# MCU.net
KiCad netlist of a schematic drawn in Altium Designer
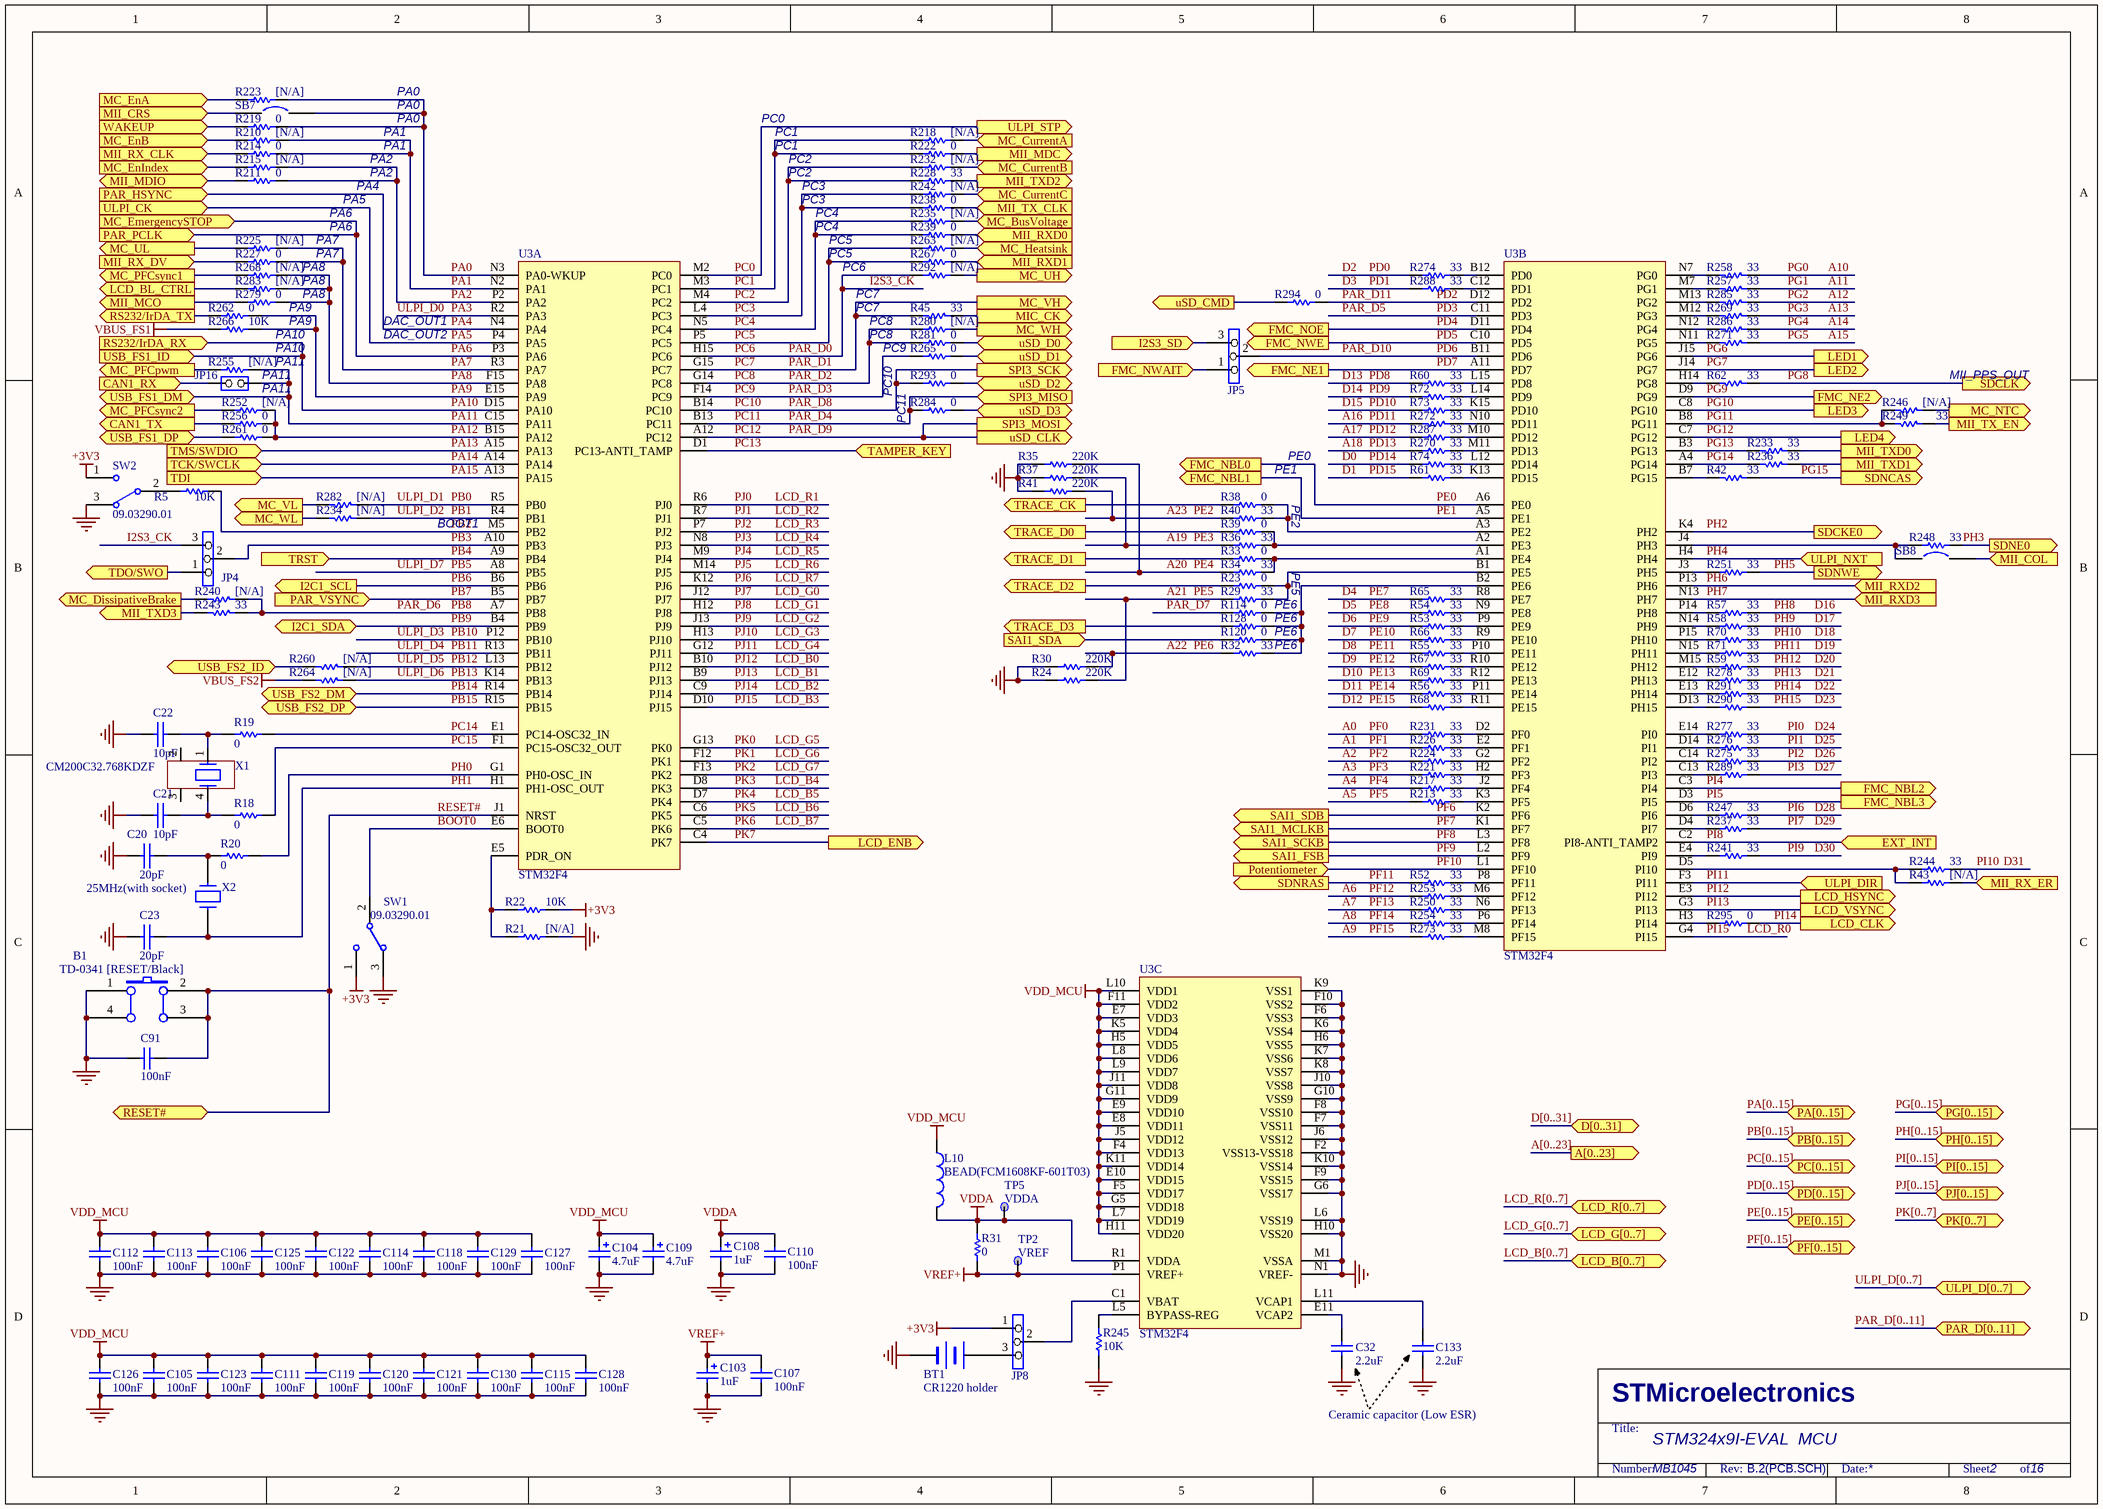
[diagram p0: MCU.SchDoc]

(export (version "E")
  (design (tool "Eeschema 10.0.6"))
  (components
    (comp (ref "B1")
      (value "TD-0341 [RESET/Black]")
      (footprint "PB10")
      (description "SE PUSHBUTTON")
      (libsource (lib "Documents") (part "SW PUSHBUTTON"))
    )
    (comp (ref "BT1")
      (value "CR1220 holder")
      (footprint "BAT_2SM_CR1220")
      (description "Battery")
      (libsource (lib "*") (part "BATTERY"))
    )
    (comp (ref "C20")
      (value "20pF")
      (footprint "0603C")
      (description "Capacitor")
      (libsource (lib "*") (part "CAP"))
    )
    (comp (ref "C21")
      (value "10pF")
      (footprint "0603C")
      (description "Capacitor")
      (libsource (lib "") (part "CAP_1"))
    )
    (comp (ref "C22")
      (value "10pF")
      (footprint "0603C")
      (description "Capacitor")
      (libsource (lib "") (part "CAP_1"))
    )
    (comp (ref "C23")
      (value "20pF")
      (footprint "0603C")
      (description "Capacitor")
      (libsource (lib "*") (part "CAP"))
    )
    (comp (ref "C32")
      (value "2.2uF")
      (footprint "1206C")
      (description "Capacitor")
      (fields (field (name "PUBLISHER") "Altium Limited"))
      (libsource (lib "Miscellaneous Devices") (part "Cap"))
    )
    (comp (ref "C91")
      (value "100nF")
      (footprint "0603C")
      (description "Capacitor")
      (fields (field (name "PUBLISHER") "Altium Limited"))
      (libsource (lib "Miscellaneous Devices") (part "CAP"))
    )
    (comp (ref "C103")
      (value "1uF")
      (footprint "TAN-A")
      (description "Polarized Capacitor (Radial)")
      (fields (field (name "PUBLISHER") "Altium Limited"))
      (libsource (lib "Miscellaneous Devices") (part "Cap Pol1"))
    )
    (comp (ref "C104")
      (value "4.7uF")
      (footprint "TAN-A")
      (description "Polarized Capacitor (Radial)")
      (fields (field (name "PUBLISHER") "Altium Limited"))
      (libsource (lib "Miscellaneous Devices") (part "Cap Pol1"))
    )
    (comp (ref "C105")
      (value "100nF")
      (footprint "0402C")
      (description "Capacitor")
      (fields (field (name "PUBLISHER") "Altium Limited"))
      (libsource (lib "Miscellaneous Devices") (part "CAP"))
    )
    (comp (ref "C106")
      (value "100nF")
      (footprint "0402C")
      (description "Capacitor")
      (fields (field (name "PUBLISHER") "Altium Limited"))
      (libsource (lib "Miscellaneous Devices") (part "CAP"))
    )
    (comp (ref "C107")
      (value "100nF")
      (footprint "0402C")
      (description "Capacitor")
      (fields (field (name "PUBLISHER") "Altium Limited"))
      (libsource (lib "Miscellaneous Devices") (part "Cap"))
    )
    (comp (ref "C108")
      (value "1uF")
      (footprint "TAN-A")
      (description "Polarized Capacitor (Radial)")
      (fields (field (name "PUBLISHER") "Altium Limited"))
      (libsource (lib "Miscellaneous Devices") (part "Cap Pol1"))
    )
    (comp (ref "C109")
      (value "4.7uF")
      (footprint "TAN-A")
      (description "Polarized Capacitor (Radial)")
      (fields (field (name "PUBLISHER") "Altium Limited"))
      (libsource (lib "Miscellaneous Devices") (part "Cap Pol1"))
    )
    (comp (ref "C110")
      (value "100nF")
      (footprint "0402C")
      (description "Capacitor")
      (fields (field (name "PUBLISHER") "Altium Limited"))
      (libsource (lib "Miscellaneous Devices") (part "Cap"))
    )
    (comp (ref "C111")
      (value "100nF")
      (footprint "0402C")
      (description "Capacitor")
      (fields (field (name "PUBLISHER") "Altium Limited"))
      (libsource (lib "Miscellaneous Devices") (part "CAP"))
    )
    (comp (ref "C112")
      (value "100nF")
      (footprint "0402C")
      (description "Capacitor")
      (fields (field (name "PUBLISHER") "Altium Limited"))
      (libsource (lib "Miscellaneous Devices") (part "CAP"))
    )
    (comp (ref "C113")
      (value "100nF")
      (footprint "0402C")
      (description "Capacitor")
      (fields (field (name "PUBLISHER") "Altium Limited"))
      (libsource (lib "Miscellaneous Devices") (part "CAP"))
    )
    (comp (ref "C114")
      (value "100nF")
      (footprint "0402C")
      (description "Capacitor")
      (fields (field (name "PUBLISHER") "Altium Limited"))
      (libsource (lib "Miscellaneous Devices") (part "CAP"))
    )
    (comp (ref "C115")
      (value "100nF")
      (footprint "0402C")
      (description "Capacitor")
      (fields (field (name "PUBLISHER") "Altium Limited"))
      (libsource (lib "Miscellaneous Devices") (part "CAP"))
    )
    (comp (ref "C118")
      (value "100nF")
      (footprint "0402C")
      (description "Capacitor")
      (fields (field (name "PUBLISHER") "Altium Limited"))
      (libsource (lib "Miscellaneous Devices") (part "CAP"))
    )
    (comp (ref "C119")
      (value "100nF")
      (footprint "0402C")
      (description "Capacitor")
      (fields (field (name "PUBLISHER") "Altium Limited"))
      (libsource (lib "Miscellaneous Devices") (part "CAP"))
    )
    (comp (ref "C120")
      (value "100nF")
      (footprint "0402C")
      (description "Capacitor")
      (fields (field (name "PUBLISHER") "Altium Limited"))
      (libsource (lib "Miscellaneous Devices") (part "CAP"))
    )
    (comp (ref "C121")
      (value "100nF")
      (footprint "0402C")
      (description "Capacitor")
      (fields (field (name "PUBLISHER") "Altium Limited"))
      (libsource (lib "Miscellaneous Devices") (part "CAP"))
    )
    (comp (ref "C122")
      (value "100nF")
      (footprint "0402C")
      (description "Capacitor")
      (fields (field (name "PUBLISHER") "Altium Limited"))
      (libsource (lib "Miscellaneous Devices") (part "CAP"))
    )
    (comp (ref "C123")
      (value "100nF")
      (footprint "0402C")
      (description "Capacitor")
      (fields (field (name "PUBLISHER") "Altium Limited"))
      (libsource (lib "Miscellaneous Devices") (part "CAP"))
    )
    (comp (ref "C125")
      (value "100nF")
      (footprint "0402C")
      (description "Capacitor")
      (fields (field (name "PUBLISHER") "Altium Limited"))
      (libsource (lib "Miscellaneous Devices") (part "CAP"))
    )
    (comp (ref "C126")
      (value "100nF")
      (footprint "0402C")
      (description "Capacitor")
      (fields (field (name "PUBLISHER") "Altium Limited"))
      (libsource (lib "Miscellaneous Devices") (part "CAP"))
    )
    (comp (ref "C127")
      (value "100nF")
      (footprint "0402C")
      (description "Capacitor")
      (fields (field (name "PUBLISHER") "Altium Limited"))
      (libsource (lib "Miscellaneous Devices") (part "CAP"))
    )
    (comp (ref "C128")
      (value "100nF")
      (footprint "0402C")
      (description "Capacitor")
      (fields (field (name "PUBLISHER") "Altium Limited"))
      (libsource (lib "Miscellaneous Devices") (part "CAP"))
    )
    (comp (ref "C129")
      (value "100nF")
      (footprint "0402C")
      (description "Capacitor")
      (fields (field (name "PUBLISHER") "Altium Limited"))
      (libsource (lib "Miscellaneous Devices") (part "CAP"))
    )
    (comp (ref "C130")
      (value "100nF")
      (footprint "0402C")
      (description "Capacitor")
      (fields (field (name "PUBLISHER") "Altium Limited"))
      (libsource (lib "Miscellaneous Devices") (part "CAP"))
    )
    (comp (ref "C133")
      (value "2.2uF")
      (footprint "1206C")
      (description "Capacitor")
      (fields (field (name "PUBLISHER") "Altium Limited"))
      (libsource (lib "Miscellaneous Devices") (part "Cap"))
    )
    (comp (ref "JP4") (value "~") (footprint "SIP3") (libsource (lib "") (part "Jumper3_1")))
    (comp (ref "JP5") (value "~") (footprint "SIP3") (libsource (lib "") (part "Jumper3_1")))
    (comp (ref "JP8") (value "~") (footprint "SIP3") (libsource (lib "STR910_SCHLIB") (part "Jumper3")))
    (comp (ref "JP16") (value "~") (footprint "SIP2") (libsource (lib "*") (part "JP2")))
    (comp (ref "L10")
      (value "BEAD(FCM1608KF-601T03)")
      (footprint "0603L")
      (description "Inductor")
      (fields (field (name "PUBLISHER") "Altium Limited"))
      (libsource (lib "Miscellaneous Devices") (part "Inductor"))
    )
    (comp (ref "R5")
      (value "10K")
      (footprint "0603R")
      (description "Resistor")
      (fields (field (name "PUBLISHER") "Altium Limited"))
      (libsource (lib "Miscellaneous Devices") (part "Res1"))
    )
    (comp (ref "R18")
      (value "0")
      (footprint "0603R")
      (description "Resistor")
      (fields (field (name "PUBLISHER") "Altium Limited"))
      (libsource (lib "") (part "Res1_1"))
    )
    (comp (ref "R19")
      (value "0")
      (footprint "0603R")
      (description "Resistor")
      (fields (field (name "PUBLISHER") "Altium Limited"))
      (libsource (lib "") (part "Res1_1"))
    )
    (comp (ref "R20")
      (value "0")
      (footprint "0603R")
      (description "Resistor")
      (fields (field (name "PUBLISHER") "Altium Limited"))
      (libsource (lib "Miscellaneous Devices") (part "Res1"))
    )
    (comp (ref "R21")
      (value "[N/A]")
      (footprint "0603R")
      (description "Resistor")
      (fields (field (name "PUBLISHER") "Altium Limited"))
      (libsource (lib "Miscellaneous Devices") (part "Res1"))
    )
    (comp (ref "R22")
      (value "10K")
      (footprint "0603R")
      (description "Resistor")
      (fields (field (name "PUBLISHER") "Altium Limited"))
      (libsource (lib "Miscellaneous Devices") (part "Res1"))
    )
    (comp (ref "R23")
      (value "0")
      (footprint "0603R")
      (description "Resistor")
      (fields (field (name "PUBLISHER") "Altium Limited"))
      (libsource (lib "Miscellaneous Devices") (part "Res1"))
    )
    (comp (ref "R24")
      (value "220K")
      (footprint "0603R")
      (description "Resistor")
      (fields (field (name "PUBLISHER") "Altium Limited"))
      (libsource (lib "Miscellaneous Devices") (part "res1"))
    )
    (comp (ref "R29")
      (value "33")
      (footprint "0402R")
      (description "Resistor")
      (fields (field (name "PUBLISHER") "Altium Limited"))
      (libsource (lib "Miscellaneous Devices") (part "Res1"))
    )
    (comp (ref "R30")
      (value "220K")
      (footprint "0603R")
      (description "Resistor")
      (fields (field (name "PUBLISHER") "Altium Limited"))
      (libsource (lib "Miscellaneous Devices") (part "res1"))
    )
    (comp (ref "R31")
      (value "0")
      (footprint "0603R")
      (description "Resistor")
      (fields (field (name "PUBLISHER") "Altium Limited"))
      (libsource (lib "Miscellaneous Devices") (part "Res1"))
    )
    (comp (ref "R32")
      (value "33")
      (footprint "0402R")
      (description "Resistor")
      (fields (field (name "PUBLISHER") "Altium Limited"))
      (libsource (lib "Miscellaneous Devices") (part "Res1"))
    )
    (comp (ref "R33")
      (value "0")
      (footprint "0603R")
      (description "Resistor")
      (fields (field (name "PUBLISHER") "Altium Limited"))
      (libsource (lib "Miscellaneous Devices") (part "Res1"))
    )
    (comp (ref "R34")
      (value "33")
      (footprint "0402R")
      (description "Resistor")
      (fields (field (name "PUBLISHER") "Altium Limited"))
      (libsource (lib "Miscellaneous Devices") (part "Res1"))
    )
    (comp (ref "R35")
      (value "220K")
      (footprint "0603R")
      (description "Resistor")
      (fields (field (name "PUBLISHER") "Altium Limited"))
      (libsource (lib "Miscellaneous Devices") (part "res1"))
    )
    (comp (ref "R36")
      (value "33")
      (footprint "0402R")
      (description "Resistor")
      (fields (field (name "PUBLISHER") "Altium Limited"))
      (libsource (lib "Miscellaneous Devices") (part "Res1"))
    )
    (comp (ref "R37")
      (value "220K")
      (footprint "0603R")
      (description "Resistor")
      (fields (field (name "PUBLISHER") "Altium Limited"))
      (libsource (lib "Miscellaneous Devices") (part "res1"))
    )
    (comp (ref "R38")
      (value "0")
      (footprint "0603R")
      (description "Resistor")
      (fields (field (name "PUBLISHER") "Altium Limited"))
      (libsource (lib "Miscellaneous Devices") (part "Res1"))
    )
    (comp (ref "R39")
      (value "0")
      (footprint "0603R")
      (description "Resistor")
      (fields (field (name "PUBLISHER") "Altium Limited"))
      (libsource (lib "Miscellaneous Devices") (part "Res1"))
    )
    (comp (ref "R40")
      (value "33")
      (footprint "0402R")
      (description "Resistor")
      (fields (field (name "PUBLISHER") "Altium Limited"))
      (libsource (lib "Miscellaneous Devices") (part "Res1"))
    )
    (comp (ref "R41")
      (value "220K")
      (footprint "0603R")
      (description "Resistor")
      (fields (field (name "PUBLISHER") "Altium Limited"))
      (libsource (lib "Miscellaneous Devices") (part "res1"))
    )
    (comp (ref "R42")
      (value "33")
      (footprint "0402R")
      (description "Resistor")
      (fields (field (name "PUBLISHER") "Altium Limited"))
      (libsource (lib "Miscellaneous Devices") (part "Res1"))
    )
    (comp (ref "R43")
      (value "[N/A]")
      (footprint "0603R")
      (description "Resistor")
      (fields (field (name "PUBLISHER") "Altium Limited"))
      (libsource (lib "Miscellaneous Devices") (part "Res1"))
    )
    (comp (ref "R45")
      (value "33")
      (footprint "0603R")
      (description "Resistor")
      (fields (field (name "PUBLISHER") "Altium Limited"))
      (libsource (lib "Miscellaneous Devices") (part "Res1"))
    )
    (comp (ref "R52")
      (value "33")
      (footprint "0402R")
      (description "Resistor")
      (fields (field (name "PUBLISHER") "Altium Limited"))
      (libsource (lib "Miscellaneous Devices") (part "Res1"))
    )
    (comp (ref "R53")
      (value "33")
      (footprint "0402R")
      (description "Resistor")
      (fields (field (name "PUBLISHER") "Altium Limited"))
      (libsource (lib "Miscellaneous Devices") (part "Res1"))
    )
    (comp (ref "R54")
      (value "33")
      (footprint "0402R")
      (description "Resistor")
      (fields (field (name "PUBLISHER") "Altium Limited"))
      (libsource (lib "Miscellaneous Devices") (part "Res1"))
    )
    (comp (ref "R55")
      (value "33")
      (footprint "0402R")
      (description "Resistor")
      (fields (field (name "PUBLISHER") "Altium Limited"))
      (libsource (lib "Miscellaneous Devices") (part "Res1"))
    )
    (comp (ref "R56")
      (value "33")
      (footprint "0402R")
      (description "Resistor")
      (fields (field (name "PUBLISHER") "Altium Limited"))
      (libsource (lib "Miscellaneous Devices") (part "Res1"))
    )
    (comp (ref "R57")
      (value "33")
      (footprint "0402R")
      (description "Resistor")
      (fields (field (name "PUBLISHER") "Altium Limited"))
      (libsource (lib "Miscellaneous Devices") (part "Res1"))
    )
    (comp (ref "R58")
      (value "33")
      (footprint "0402R")
      (description "Resistor")
      (fields (field (name "PUBLISHER") "Altium Limited"))
      (libsource (lib "Miscellaneous Devices") (part "Res1"))
    )
    (comp (ref "R59")
      (value "33")
      (footprint "0402R")
      (description "Resistor")
      (fields (field (name "PUBLISHER") "Altium Limited"))
      (libsource (lib "Miscellaneous Devices") (part "Res1"))
    )
    (comp (ref "R60")
      (value "33")
      (footprint "0402R")
      (description "Resistor")
      (fields (field (name "PUBLISHER") "Altium Limited"))
      (libsource (lib "Miscellaneous Devices") (part "Res1"))
    )
    (comp (ref "R61")
      (value "33")
      (footprint "0402R")
      (description "Resistor")
      (fields (field (name "PUBLISHER") "Altium Limited"))
      (libsource (lib "Miscellaneous Devices") (part "Res1"))
    )
    (comp (ref "R62")
      (value "33")
      (footprint "0402R")
      (description "Resistor")
      (fields (field (name "PUBLISHER") "Altium Limited"))
      (libsource (lib "Miscellaneous Devices") (part "Res1"))
    )
    (comp (ref "R65")
      (value "33")
      (footprint "0402R")
      (description "Resistor")
      (fields (field (name "PUBLISHER") "Altium Limited"))
      (libsource (lib "Miscellaneous Devices") (part "Res1"))
    )
    (comp (ref "R66")
      (value "33")
      (footprint "0402R")
      (description "Resistor")
      (fields (field (name "PUBLISHER") "Altium Limited"))
      (libsource (lib "Miscellaneous Devices") (part "Res1"))
    )
    (comp (ref "R67")
      (value "33")
      (footprint "0402R")
      (description "Resistor")
      (fields (field (name "PUBLISHER") "Altium Limited"))
      (libsource (lib "Miscellaneous Devices") (part "Res1"))
    )
    (comp (ref "R68")
      (value "33")
      (footprint "0402R")
      (description "Resistor")
      (fields (field (name "PUBLISHER") "Altium Limited"))
      (libsource (lib "Miscellaneous Devices") (part "Res1"))
    )
    (comp (ref "R69")
      (value "33")
      (footprint "0402R")
      (description "Resistor")
      (fields (field (name "PUBLISHER") "Altium Limited"))
      (libsource (lib "Miscellaneous Devices") (part "Res1"))
    )
    (comp (ref "R70")
      (value "33")
      (footprint "0402R")
      (description "Resistor")
      (fields (field (name "PUBLISHER") "Altium Limited"))
      (libsource (lib "Miscellaneous Devices") (part "Res1"))
    )
    (comp (ref "R71")
      (value "33")
      (footprint "0402R")
      (description "Resistor")
      (fields (field (name "PUBLISHER") "Altium Limited"))
      (libsource (lib "Miscellaneous Devices") (part "Res1"))
    )
    (comp (ref "R72")
      (value "33")
      (footprint "0402R")
      (description "Resistor")
      (fields (field (name "PUBLISHER") "Altium Limited"))
      (libsource (lib "Miscellaneous Devices") (part "Res1"))
    )
    (comp (ref "R73")
      (value "33")
      (footprint "0402R")
      (description "Resistor")
      (fields (field (name "PUBLISHER") "Altium Limited"))
      (libsource (lib "Miscellaneous Devices") (part "Res1"))
    )
    (comp (ref "R74")
      (value "33")
      (footprint "0402R")
      (description "Resistor")
      (fields (field (name "PUBLISHER") "Altium Limited"))
      (libsource (lib "Miscellaneous Devices") (part "Res1"))
    )
    (comp (ref "R114")
      (value "0")
      (footprint "0603R")
      (description "Resistor")
      (fields (field (name "PUBLISHER") "Altium Limited"))
      (libsource (lib "Miscellaneous Devices") (part "Res1"))
    )
    (comp (ref "R120")
      (value "0")
      (footprint "0603R")
      (description "Resistor")
      (fields (field (name "PUBLISHER") "Altium Limited"))
      (libsource (lib "Miscellaneous Devices") (part "Res1"))
    )
    (comp (ref "R128")
      (value "0")
      (footprint "0603R")
      (description "Resistor")
      (fields (field (name "PUBLISHER") "Altium Limited"))
      (libsource (lib "Miscellaneous Devices") (part "Res1"))
    )
    (comp (ref "R210")
      (value "[N/A]")
      (footprint "0603R")
      (description "Resistor")
      (fields (field (name "PUBLISHER") "Altium Limited"))
      (libsource (lib "Miscellaneous Devices") (part "Res1"))
    )
    (comp (ref "R211")
      (value "0")
      (footprint "0603R")
      (description "Resistor")
      (fields (field (name "PUBLISHER") "Altium Limited"))
      (libsource (lib "Miscellaneous Devices") (part "Res1"))
    )
    (comp (ref "R213")
      (value "33")
      (footprint "0402R")
      (description "Resistor")
      (fields (field (name "PUBLISHER") "Altium Limited"))
      (libsource (lib "Miscellaneous Devices") (part "Res1"))
    )
    (comp (ref "R214")
      (value "0")
      (footprint "0603R")
      (description "Resistor")
      (fields (field (name "PUBLISHER") "Altium Limited"))
      (libsource (lib "Miscellaneous Devices") (part "Res1"))
    )
    (comp (ref "R215")
      (value "[N/A]")
      (footprint "0603R")
      (description "Resistor")
      (fields (field (name "PUBLISHER") "Altium Limited"))
      (libsource (lib "Miscellaneous Devices") (part "Res1"))
    )
    (comp (ref "R217")
      (value "33")
      (footprint "0402R")
      (description "Resistor")
      (fields (field (name "PUBLISHER") "Altium Limited"))
      (libsource (lib "Miscellaneous Devices") (part "Res1"))
    )
    (comp (ref "R218")
      (value "[N/A]")
      (footprint "0603R")
      (description "Resistor")
      (fields (field (name "PUBLISHER") "Altium Limited"))
      (libsource (lib "Miscellaneous Devices") (part "Res1"))
    )
    (comp (ref "R219")
      (value "0")
      (footprint "0603R")
      (description "Resistor")
      (fields (field (name "PUBLISHER") "Altium Limited"))
      (libsource (lib "Miscellaneous Devices") (part "Res1"))
    )
    (comp (ref "R221")
      (value "33")
      (footprint "0402R")
      (description "Resistor")
      (fields (field (name "PUBLISHER") "Altium Limited"))
      (libsource (lib "Miscellaneous Devices") (part "Res1"))
    )
    (comp (ref "R222")
      (value "0")
      (footprint "0603R")
      (description "Resistor")
      (fields (field (name "PUBLISHER") "Altium Limited"))
      (libsource (lib "Miscellaneous Devices") (part "Res1"))
    )
    (comp (ref "R223")
      (value "[N/A]")
      (footprint "0603R")
      (description "Resistor")
      (fields (field (name "PUBLISHER") "Altium Limited"))
      (libsource (lib "Miscellaneous Devices") (part "Res1"))
    )
    (comp (ref "R224")
      (value "33")
      (footprint "0402R")
      (description "Resistor")
      (fields (field (name "PUBLISHER") "Altium Limited"))
      (libsource (lib "Miscellaneous Devices") (part "Res1"))
    )
    (comp (ref "R225")
      (value "[N/A]")
      (footprint "0603R")
      (description "Resistor")
      (fields (field (name "PUBLISHER") "Altium Limited"))
      (libsource (lib "Miscellaneous Devices") (part "Res1"))
    )
    (comp (ref "R226")
      (value "33")
      (footprint "0402R")
      (description "Resistor")
      (fields (field (name "PUBLISHER") "Altium Limited"))
      (libsource (lib "Miscellaneous Devices") (part "Res1"))
    )
    (comp (ref "R227")
      (value "0")
      (footprint "0603R")
      (description "Resistor")
      (fields (field (name "PUBLISHER") "Altium Limited"))
      (libsource (lib "Miscellaneous Devices") (part "Res1"))
    )
    (comp (ref "R228")
      (value "33")
      (footprint "0603R")
      (description "Resistor")
      (fields (field (name "PUBLISHER") "Altium Limited"))
      (libsource (lib "Miscellaneous Devices") (part "Res1"))
    )
    (comp (ref "R231")
      (value "33")
      (footprint "0402R")
      (description "Resistor")
      (fields (field (name "PUBLISHER") "Altium Limited"))
      (libsource (lib "Miscellaneous Devices") (part "Res1"))
    )
    (comp (ref "R232")
      (value "[N/A]")
      (footprint "0603R")
      (description "Resistor")
      (fields (field (name "PUBLISHER") "Altium Limited"))
      (libsource (lib "Miscellaneous Devices") (part "Res1"))
    )
    (comp (ref "R233")
      (value "33")
      (footprint "0603R")
      (description "Resistor")
      (fields (field (name "PUBLISHER") "Altium Limited"))
      (libsource (lib "Miscellaneous Devices") (part "Res1"))
    )
    (comp (ref "R234")
      (value "[N/A]")
      (footprint "0603R")
      (description "Resistor")
      (fields (field (name "PUBLISHER") "Altium Limited"))
      (libsource (lib "Miscellaneous Devices") (part "Res1"))
    )
    (comp (ref "R235")
      (value "[N/A]")
      (footprint "0603R")
      (description "Resistor")
      (fields (field (name "PUBLISHER") "Altium Limited"))
      (libsource (lib "Miscellaneous Devices") (part "Res1"))
    )
    (comp (ref "R236")
      (value "33")
      (footprint "0603R")
      (description "Resistor")
      (fields (field (name "PUBLISHER") "Altium Limited"))
      (libsource (lib "Miscellaneous Devices") (part "Res1"))
    )
    (comp (ref "R237")
      (value "33")
      (footprint "0402R")
      (description "Resistor")
      (fields (field (name "PUBLISHER") "Altium Limited"))
      (libsource (lib "Miscellaneous Devices") (part "Res1"))
    )
    (comp (ref "R238")
      (value "0")
      (footprint "0603R")
      (description "Resistor")
      (fields (field (name "PUBLISHER") "Altium Limited"))
      (libsource (lib "Miscellaneous Devices") (part "Res1"))
    )
    (comp (ref "R239")
      (value "0")
      (footprint "0603R")
      (description "Resistor")
      (fields (field (name "PUBLISHER") "Altium Limited"))
      (libsource (lib "Miscellaneous Devices") (part "Res1"))
    )
    (comp (ref "R240")
      (value "[N/A]")
      (footprint "0603R")
      (description "Resistor")
      (fields (field (name "PUBLISHER") "Altium Limited"))
      (libsource (lib "Miscellaneous Devices") (part "Res1"))
    )
    (comp (ref "R241")
      (value "33")
      (footprint "0402R")
      (description "Resistor")
      (fields (field (name "PUBLISHER") "Altium Limited"))
      (libsource (lib "Miscellaneous Devices") (part "Res1"))
    )
    (comp (ref "R242")
      (value "[N/A]")
      (footprint "0603R")
      (description "Resistor")
      (fields (field (name "PUBLISHER") "Altium Limited"))
      (libsource (lib "Miscellaneous Devices") (part "Res1"))
    )
    (comp (ref "R243")
      (value "33")
      (footprint "0603R")
      (description "Resistor")
      (fields (field (name "PUBLISHER") "Altium Limited"))
      (libsource (lib "Miscellaneous Devices") (part "Res1"))
    )
    (comp (ref "R244")
      (value "33")
      (footprint "0402R")
      (description "Resistor")
      (fields (field (name "PUBLISHER") "Altium Limited"))
      (libsource (lib "Miscellaneous Devices") (part "Res1"))
    )
    (comp (ref "R245")
      (value "10K")
      (footprint "0603R")
      (description "Resistor")
      (fields (field (name "PUBLISHER") "Altium Limited"))
      (libsource (lib "Miscellaneous Devices") (part "Res1"))
    )
    (comp (ref "R246")
      (value "[N/A]")
      (footprint "0603R")
      (description "Resistor")
      (fields (field (name "PUBLISHER") "Altium Limited"))
      (libsource (lib "Miscellaneous Devices") (part "Res1"))
    )
    (comp (ref "R247")
      (value "33")
      (footprint "0402R")
      (description "Resistor")
      (fields (field (name "PUBLISHER") "Altium Limited"))
      (libsource (lib "Miscellaneous Devices") (part "Res1"))
    )
    (comp (ref "R248")
      (value "33")
      (footprint "0402R")
      (description "Resistor")
      (fields (field (name "PUBLISHER") "Altium Limited"))
      (libsource (lib "Miscellaneous Devices") (part "Res1"))
    )
    (comp (ref "R249")
      (value "33")
      (footprint "0603R")
      (description "Resistor")
      (fields (field (name "PUBLISHER") "Altium Limited"))
      (libsource (lib "Miscellaneous Devices") (part "Res1"))
    )
    (comp (ref "R250")
      (value "33")
      (footprint "0402R")
      (description "Resistor")
      (fields (field (name "PUBLISHER") "Altium Limited"))
      (libsource (lib "Miscellaneous Devices") (part "Res1"))
    )
    (comp (ref "R251")
      (value "33")
      (footprint "0402R")
      (description "Resistor")
      (fields (field (name "PUBLISHER") "Altium Limited"))
      (libsource (lib "Miscellaneous Devices") (part "Res1"))
    )
    (comp (ref "R252")
      (value "[N/A]")
      (footprint "0603R")
      (description "Resistor")
      (fields (field (name "PUBLISHER") "Altium Limited"))
      (libsource (lib "Miscellaneous Devices") (part "Res1"))
    )
    (comp (ref "R253")
      (value "33")
      (footprint "0402R")
      (description "Resistor")
      (fields (field (name "PUBLISHER") "Altium Limited"))
      (libsource (lib "Miscellaneous Devices") (part "Res1"))
    )
    (comp (ref "R254")
      (value "33")
      (footprint "0402R")
      (description "Resistor")
      (fields (field (name "PUBLISHER") "Altium Limited"))
      (libsource (lib "Miscellaneous Devices") (part "Res1"))
    )
    (comp (ref "R255")
      (value "[N/A]")
      (footprint "0603R")
      (description "Resistor")
      (fields (field (name "PUBLISHER") "Altium Limited"))
      (libsource (lib "Miscellaneous Devices") (part "Res1"))
    )
    (comp (ref "R256")
      (value "0")
      (footprint "0603R")
      (description "Resistor")
      (fields (field (name "PUBLISHER") "Altium Limited"))
      (libsource (lib "Miscellaneous Devices") (part "Res1"))
    )
    (comp (ref "R257")
      (value "33")
      (footprint "0402R")
      (description "Resistor")
      (fields (field (name "PUBLISHER") "Altium Limited"))
      (libsource (lib "Miscellaneous Devices") (part "Res1"))
    )
    (comp (ref "R258")
      (value "33")
      (footprint "0402R")
      (description "Resistor")
      (fields (field (name "PUBLISHER") "Altium Limited"))
      (libsource (lib "Miscellaneous Devices") (part "Res1"))
    )
    (comp (ref "R260")
      (value "[N/A]")
      (footprint "0603R")
      (description "Resistor")
      (fields (field (name "PUBLISHER") "Altium Limited"))
      (libsource (lib "Miscellaneous Devices") (part "Res1"))
    )
    (comp (ref "R261")
      (value "0")
      (footprint "0603R")
      (description "Resistor")
      (fields (field (name "PUBLISHER") "Altium Limited"))
      (libsource (lib "Miscellaneous Devices") (part "Res1"))
    )
    (comp (ref "R262")
      (value "0")
      (footprint "0603R")
      (description "Resistor")
      (fields (field (name "PUBLISHER") "Altium Limited"))
      (libsource (lib "Miscellaneous Devices") (part "Res1"))
    )
    (comp (ref "R263")
      (value "[N/A]")
      (footprint "0603R")
      (description "Resistor")
      (fields (field (name "PUBLISHER") "Altium Limited"))
      (libsource (lib "Miscellaneous Devices") (part "Res1"))
    )
    (comp (ref "R264")
      (value "[N/A]")
      (footprint "0603R")
      (description "Resistor")
      (fields (field (name "PUBLISHER") "Altium Limited"))
      (libsource (lib "Miscellaneous Devices") (part "Res1"))
    )
    (comp (ref "R265")
      (value "0")
      (footprint "0603R")
      (description "Resistor")
      (fields (field (name "PUBLISHER") "Altium Limited"))
      (libsource (lib "Miscellaneous Devices") (part "Res1"))
    )
    (comp (ref "R266")
      (value "10K")
      (footprint "0603R")
      (description "Resistor")
      (fields (field (name "PUBLISHER") "Altium Limited"))
      (libsource (lib "Miscellaneous Devices") (part "res1"))
    )
    (comp (ref "R267")
      (value "0")
      (footprint "0603R")
      (description "Resistor")
      (fields (field (name "PUBLISHER") "Altium Limited"))
      (libsource (lib "Miscellaneous Devices") (part "Res1"))
    )
    (comp (ref "R268")
      (value "[N/A]")
      (footprint "0603R")
      (description "Resistor")
      (fields (field (name "PUBLISHER") "Altium Limited"))
      (libsource (lib "Miscellaneous Devices") (part "Res1"))
    )
    (comp (ref "R269")
      (value "33")
      (footprint "0402R")
      (description "Resistor")
      (fields (field (name "PUBLISHER") "Altium Limited"))
      (libsource (lib "Miscellaneous Devices") (part "Res1"))
    )
    (comp (ref "R270")
      (value "33")
      (footprint "0402R")
      (description "Resistor")
      (fields (field (name "PUBLISHER") "Altium Limited"))
      (libsource (lib "Miscellaneous Devices") (part "Res1"))
    )
    (comp (ref "R271")
      (value "33")
      (footprint "0402R")
      (description "Resistor")
      (fields (field (name "PUBLISHER") "Altium Limited"))
      (libsource (lib "Miscellaneous Devices") (part "Res1"))
    )
    (comp (ref "R272")
      (value "33")
      (footprint "0402R")
      (description "Resistor")
      (fields (field (name "PUBLISHER") "Altium Limited"))
      (libsource (lib "Miscellaneous Devices") (part "Res1"))
    )
    (comp (ref "R273")
      (value "33")
      (footprint "0402R")
      (description "Resistor")
      (fields (field (name "PUBLISHER") "Altium Limited"))
      (libsource (lib "Miscellaneous Devices") (part "Res1"))
    )
    (comp (ref "R274")
      (value "33")
      (footprint "0402R")
      (description "Resistor")
      (fields (field (name "PUBLISHER") "Altium Limited"))
      (libsource (lib "Miscellaneous Devices") (part "Res1"))
    )
    (comp (ref "R275")
      (value "33")
      (footprint "0402R")
      (description "Resistor")
      (fields (field (name "PUBLISHER") "Altium Limited"))
      (libsource (lib "Miscellaneous Devices") (part "Res1"))
    )
    (comp (ref "R276")
      (value "33")
      (footprint "0402R")
      (description "Resistor")
      (fields (field (name "PUBLISHER") "Altium Limited"))
      (libsource (lib "Miscellaneous Devices") (part "Res1"))
    )
    (comp (ref "R277")
      (value "33")
      (footprint "0402R")
      (description "Resistor")
      (fields (field (name "PUBLISHER") "Altium Limited"))
      (libsource (lib "Miscellaneous Devices") (part "Res1"))
    )
    (comp (ref "R278")
      (value "33")
      (footprint "0402R")
      (description "Resistor")
      (fields (field (name "PUBLISHER") "Altium Limited"))
      (libsource (lib "Miscellaneous Devices") (part "Res1"))
    )
    (comp (ref "R279")
      (value "0")
      (footprint "0603R")
      (description "Resistor")
      (fields (field (name "PUBLISHER") "Altium Limited"))
      (libsource (lib "Miscellaneous Devices") (part "Res1"))
    )
    (comp (ref "R280")
      (value "[N/A]")
      (footprint "0603R")
      (description "Resistor")
      (fields (field (name "PUBLISHER") "Altium Limited"))
      (libsource (lib "Miscellaneous Devices") (part "Res1"))
    )
    (comp (ref "R281")
      (value "0")
      (footprint "0603R")
      (description "Resistor")
      (fields (field (name "PUBLISHER") "Altium Limited"))
      (libsource (lib "Miscellaneous Devices") (part "Res1"))
    )
    (comp (ref "R282")
      (value "[N/A]")
      (footprint "0603R")
      (description "Resistor")
      (fields (field (name "PUBLISHER") "Altium Limited"))
      (libsource (lib "Miscellaneous Devices") (part "Res1"))
    )
    (comp (ref "R283")
      (value "[N/A]")
      (footprint "0603R")
      (description "Resistor")
      (fields (field (name "PUBLISHER") "Altium Limited"))
      (libsource (lib "Miscellaneous Devices") (part "Res1"))
    )
    (comp (ref "R284")
      (value "0")
      (footprint "0603R")
      (description "Resistor")
      (fields (field (name "PUBLISHER") "Altium Limited"))
      (libsource (lib "Miscellaneous Devices") (part "Res1"))
    )
    (comp (ref "R285")
      (value "33")
      (footprint "0402R")
      (description "Resistor")
      (fields (field (name "PUBLISHER") "Altium Limited"))
      (libsource (lib "Miscellaneous Devices") (part "Res1"))
    )
    (comp (ref "R286")
      (value "33")
      (footprint "0402R")
      (description "Resistor")
      (fields (field (name "PUBLISHER") "Altium Limited"))
      (libsource (lib "Miscellaneous Devices") (part "Res1"))
    )
    (comp (ref "R287")
      (value "33")
      (footprint "0402R")
      (description "Resistor")
      (fields (field (name "PUBLISHER") "Altium Limited"))
      (libsource (lib "Miscellaneous Devices") (part "Res1"))
    )
    (comp (ref "R288")
      (value "33")
      (footprint "0402R")
      (description "Resistor")
      (fields (field (name "PUBLISHER") "Altium Limited"))
      (libsource (lib "Miscellaneous Devices") (part "Res1"))
    )
    (comp (ref "R289")
      (value "33")
      (footprint "0402R")
      (description "Resistor")
      (fields (field (name "PUBLISHER") "Altium Limited"))
      (libsource (lib "Miscellaneous Devices") (part "Res1"))
    )
    (comp (ref "R290")
      (value "33")
      (footprint "0402R")
      (description "Resistor")
      (fields (field (name "PUBLISHER") "Altium Limited"))
      (libsource (lib "Miscellaneous Devices") (part "Res1"))
    )
    (comp (ref "R291")
      (value "33")
      (footprint "0402R")
      (description "Resistor")
      (fields (field (name "PUBLISHER") "Altium Limited"))
      (libsource (lib "Miscellaneous Devices") (part "Res1"))
    )
    (comp (ref "R292")
      (value "[N/A]")
      (footprint "0603R")
      (description "Resistor")
      (fields (field (name "PUBLISHER") "Altium Limited"))
      (libsource (lib "Miscellaneous Devices") (part "Res1"))
    )
    (comp (ref "R293")
      (value "0")
      (footprint "0603R")
      (description "Resistor")
      (fields (field (name "PUBLISHER") "Altium Limited"))
      (libsource (lib "Miscellaneous Devices") (part "Res1"))
    )
    (comp (ref "R294")
      (value "0")
      (footprint "0603R")
      (description "Resistor")
      (fields (field (name "PUBLISHER") "Altium Limited"))
      (libsource (lib "Miscellaneous Devices") (part "Res1"))
    )
    (comp (ref "R295")
      (value "0")
      (footprint "0603R")
      (description "Resistor")
      (fields (field (name "PUBLISHER") "Altium Limited"))
      (libsource (lib "Miscellaneous Devices") (part "Res1"))
    )
    (comp (ref "SB7")
      (value "~")
      (footprint "JP2_SMD")
      (description "Circuit Breaker")
      (fields (field (name "PUBLISHER") "Altium Limited"))
      (libsource (lib "Miscellaneous Devices") (part "Circuit Breaker"))
    )
    (comp (ref "SB8")
      (value "~")
      (footprint "JP2_SMD")
      (description "Circuit Breaker")
      (fields (field (name "PUBLISHER") "Altium Limited"))
      (libsource (lib "Miscellaneous Devices") (part "Circuit Breaker"))
    )
    (comp (ref "SW1")
      (value "09.03290.01")
      (footprint "SW1_3TH_2R54_10X2R5")
      (description "SPDT Subminiature Toggle Switch, Right Angle Mounting, Vertical Actuation")
      (fields (field (name "PUBLISHER") "Altium Limited"))
      (libsource (lib "mb1045") (part "SW-SPDT"))
    )
    (comp (ref "SW2")
      (value "09.03290.01")
      (footprint "SW1_3TH_2R54_10X2R5")
      (description "SPDT Subminiature Toggle Switch, Right Angle Mounting, Vertical Actuation")
      (fields (field (name "PUBLISHER") "Altium Limited"))
      (libsource (lib "mb1045") (part "SW-SPDT"))
    )
    (comp (ref "TP2") (value "VREF") (footprint "TP") (libsource (lib "*") (part "TP")))
    (comp (ref "TP5") (value "VDDA") (footprint "TP") (libsource (lib "*") (part "TP")))
    (comp (ref "U3")
      (value "STM32F4")
      (footprint "BGA216_0R8_13X13_SKT")
      (libsource (lib "mb1045") (part "Big_Manta_TFBGA216"))
    )
    (comp (ref "X1")
      (value "CM200C32.768KDZF")
      (footprint "XTAL_4SM_8X3R8")
      (libsource (lib "*") (part "MC306"))
    )
    (comp (ref "X2")
      (value "25MHz(with socket)")
      (footprint "XTAL_socket")
      (description "Crystal")
      (libsource (lib "*") (part "CRYSTAL"))
    )
  )
  (nets
    (net (code "1") (name "+3V3") (class "Default")
      (node (ref "JP8") (pin "1") (pintype "passive"))
      (node (ref "R22") (pin "2") (pinfunction "2_2") (pintype "passive"))
      (node (ref "SW1") (pin "1") (pintype "passive"))
      (node (ref "SW2") (pin "1") (pintype "passive"))
    )
    (net (code "3") (name "/BOOT0") (class "Default")
      (node (ref "SW1") (pin "2") (pintype "passive"))
      (node (ref "U3") (pin "E6") (pinfunction "BOOT0_E6") (pintype "passive"))
    )
    (net (code "4") (name "/CAN1_RX") (class "Default")
      (node (ref "JP16") (pin "2") (pinfunction "NO_2") (pintype "passive"))
    )
    (net (code "5") (name "/CAN1_TX") (class "Default")
      (node (ref "R256") (pin "2") (pinfunction "2_2") (pintype "passive"))
    )
    (net (code "7") (name "/FMC_NWAIT") (class "Default") (node (ref "JP5") (pin "1") (pintype "passive")))
    (net (code "8") (name "/I2S3_SD") (class "Default") (node (ref "JP5") (pin "3") (pintype "passive")))
    (net (code "9") (name "/LCD_BL_CTRL") (class "Default")
      (node (ref "R283") (pin "2") (pinfunction "2_2") (pintype "passive"))
    )
    (net (code "13") (name "/MC_BusVoltage") (class "Default")
      (node (ref "R235") (pin "1") (pinfunction "1_1") (pintype "passive"))
    )
    (net (code "14") (name "/MC_CurrentA") (class "Default")
      (node (ref "R218") (pin "1") (pinfunction "1_1") (pintype "passive"))
    )
    (net (code "15") (name "/MC_CurrentB") (class "Default")
      (node (ref "R232") (pin "1") (pinfunction "1_1") (pintype "passive"))
    )
    (net (code "16") (name "/MC_CurrentC") (class "Default")
      (node (ref "R242") (pin "1") (pinfunction "1_1") (pintype "passive"))
    )
    (net (code "17") (name "/MC_DissipativeBrake") (class "Default")
      (node (ref "R240") (pin "1") (pinfunction "1_1") (pintype "passive"))
    )
    (net (code "18") (name "/MC_EnA") (class "Default")
      (node (ref "R223") (pin "2") (pinfunction "2_2") (pintype "passive"))
    )
    (net (code "19") (name "/MC_EnB") (class "Default")
      (node (ref "R210") (pin "2") (pinfunction "2_2") (pintype "passive"))
    )
    (net (code "20") (name "/MC_EnIndex") (class "Default")
      (node (ref "R215") (pin "2") (pinfunction "2_2") (pintype "passive"))
    )
    (net (code "21") (name "/MC_Heatsink") (class "Default")
      (node (ref "R263") (pin "1") (pinfunction "1_1") (pintype "passive"))
    )
    (net (code "22") (name "/MC_NTC") (class "Default")
      (node (ref "R246") (pin "2") (pinfunction "2_2") (pintype "passive"))
    )
    (net (code "23") (name "/MC_PFCpwm") (class "Default")
      (node (ref "R255") (pin "2") (pinfunction "2_2") (pintype "passive"))
    )
    (net (code "24") (name "/MC_PFCsync1") (class "Default")
      (node (ref "R268") (pin "2") (pinfunction "2_2") (pintype "passive"))
    )
    (net (code "25") (name "/MC_PFCsync2") (class "Default")
      (node (ref "R252") (pin "2") (pinfunction "2_2") (pintype "passive"))
    )
    (net (code "26") (name "/MC_UH") (class "Default")
      (node (ref "R292") (pin "1") (pinfunction "1_1") (pintype "passive"))
    )
    (net (code "27") (name "/MC_UL") (class "Default")
      (node (ref "R225") (pin "2") (pinfunction "2_2") (pintype "passive"))
    )
    (net (code "28") (name "/MC_VL") (class "Default")
      (node (ref "R282") (pin "1") (pinfunction "1_1") (pintype "passive"))
    )
    (net (code "29") (name "/MC_WH") (class "Default")
      (node (ref "R280") (pin "1") (pinfunction "1_1") (pintype "passive"))
    )
    (net (code "30") (name "/MC_WL") (class "Default")
      (node (ref "R234") (pin "1") (pinfunction "1_1") (pintype "passive"))
    )
    (net (code "31") (name "/MIC_CK") (class "Default")
      (node (ref "R45") (pin "2") (pinfunction "2_2") (pintype "passive"))
    )
    (net (code "32") (name "/MII_COL") (class "Default")
      (node (ref "SB8") (pin "2") (pinfunction "2_2") (pintype "passive"))
    )
    (net (code "33") (name "/MII_CRS") (class "Default")
      (node (ref "SB7") (pin "1") (pinfunction "1_1") (pintype "passive"))
    )
    (net (code "34") (name "/MII_MCO") (class "Default")
      (node (ref "R279") (pin "2") (pinfunction "2_2") (pintype "passive"))
    )
    (net (code "35") (name "/MII_MDC") (class "Default")
      (node (ref "R222") (pin "1") (pinfunction "1_1") (pintype "passive"))
    )
    (net (code "36") (name "/MII_MDIO") (class "Default")
      (node (ref "R211") (pin "2") (pinfunction "2_2") (pintype "passive"))
    )
    (net (code "37") (name "/MII_RXD0") (class "Default")
      (node (ref "R239") (pin "1") (pinfunction "1_1") (pintype "passive"))
    )
    (net (code "38") (name "/MII_RXD1") (class "Default")
      (node (ref "R267") (pin "1") (pinfunction "1_1") (pintype "passive"))
    )
    (net (code "39") (name "/MII_RX_CLK") (class "Default")
      (node (ref "R214") (pin "2") (pinfunction "2_2") (pintype "passive"))
    )
    (net (code "40") (name "/MII_RX_DV") (class "Default")
      (node (ref "R227") (pin "2") (pinfunction "2_2") (pintype "passive"))
    )
    (net (code "41") (name "/MII_RX_ER") (class "Default")
      (node (ref "R43") (pin "1") (pinfunction "1_1") (pintype "passive"))
    )
    (net (code "42") (name "/MII_TXD0") (class "Default")
      (node (ref "R233") (pin "2") (pinfunction "2_2") (pintype "passive"))
    )
    (net (code "43") (name "/MII_TXD1") (class "Default")
      (node (ref "R236") (pin "2") (pinfunction "2_2") (pintype "passive"))
    )
    (net (code "44") (name "/MII_TXD2") (class "Default")
      (node (ref "R228") (pin "1") (pinfunction "1_1") (pintype "passive"))
    )
    (net (code "45") (name "/MII_TXD3") (class "Default")
      (node (ref "R243") (pin "1") (pinfunction "1_1") (pintype "passive"))
    )
    (net (code "46") (name "/MII_TX_CLK") (class "Default")
      (node (ref "R238") (pin "1") (pinfunction "1_1") (pintype "passive"))
    )
    (net (code "47") (name "/MII_TX_EN") (class "Default")
      (node (ref "R249") (pin "2") (pinfunction "2_2") (pintype "passive"))
    )
    (net (code "48") (name "/PA0") (class "Default")
      (node (ref "R219") (pin "1") (pinfunction "1_1") (pintype "passive"))
      (node (ref "R223") (pin "1") (pinfunction "1_1") (pintype "passive"))
      (node (ref "SB7") (pin "2") (pinfunction "2_2") (pintype "passive"))
      (node (ref "U3") (pin "N3") (pinfunction "PA0-WKUP_N3") (pintype "passive"))
    )
    (net (code "49") (name "/PA1") (class "Default")
      (node (ref "R210") (pin "1") (pinfunction "1_1") (pintype "passive"))
      (node (ref "R214") (pin "1") (pinfunction "1_1") (pintype "passive"))
      (node (ref "U3") (pin "N2") (pinfunction "PA1_N2") (pintype "passive"))
    )
    (net (code "50") (name "/PA2") (class "Default")
      (node (ref "R211") (pin "1") (pinfunction "1_1") (pintype "passive"))
      (node (ref "R215") (pin "1") (pinfunction "1_1") (pintype "passive"))
      (node (ref "U3") (pin "P2") (pinfunction "PA2_P2") (pintype "passive"))
    )
    (net (code "51") (name "/PA3") (class "Default")
      (node (ref "U3") (pin "R2") (pinfunction "PA3_R2") (pintype "passive"))
    )
    (net (code "52") (name "/PA4") (class "Default")
      (node (ref "U3") (pin "N4") (pinfunction "PA4_N4") (pintype "passive"))
    )
    (net (code "53") (name "/PA5") (class "Default")
      (node (ref "U3") (pin "P4") (pinfunction "PA5_P4") (pintype "passive"))
    )
    (net (code "54") (name "/PA6") (class "Default")
      (node (ref "U3") (pin "P3") (pinfunction "PA6_P3") (pintype "passive"))
    )
    (net (code "55") (name "/PA7") (class "Default")
      (node (ref "R225") (pin "1") (pinfunction "1_1") (pintype "passive"))
      (node (ref "R227") (pin "1") (pinfunction "1_1") (pintype "passive"))
      (node (ref "U3") (pin "R3") (pinfunction "PA7_R3") (pintype "passive"))
    )
    (net (code "56") (name "/PA8") (class "Default")
      (node (ref "R268") (pin "1") (pinfunction "1_1") (pintype "passive"))
      (node (ref "R279") (pin "1") (pinfunction "1_1") (pintype "passive"))
      (node (ref "R283") (pin "1") (pinfunction "1_1") (pintype "passive"))
      (node (ref "U3") (pin "F15") (pinfunction "PA8_F15") (pintype "passive"))
    )
    (net (code "57") (name "/PA9") (class "Default")
      (node (ref "R262") (pin "1") (pinfunction "1_1") (pintype "passive"))
      (node (ref "R266") (pin "1") (pinfunction "1_1") (pintype "passive"))
      (node (ref "U3") (pin "E15") (pinfunction "PA9_E15") (pintype "passive"))
    )
    (net (code "58") (name "/PA10") (class "Default")
      (node (ref "U3") (pin "D15") (pinfunction "PA10_D15") (pintype "passive"))
    )
    (net (code "59") (name "/PA11") (class "Default")
      (node (ref "JP16") (pin "1") (pinfunction "COMMON_1") (pintype "passive"))
      (node (ref "R255") (pin "1") (pinfunction "1_1") (pintype "passive"))
      (node (ref "U3") (pin "C15") (pinfunction "PA11_C15") (pintype "passive"))
    )
    (net (code "60") (name "/PA12") (class "Default")
      (node (ref "R252") (pin "1") (pinfunction "1_1") (pintype "passive"))
      (node (ref "R256") (pin "1") (pinfunction "1_1") (pintype "passive"))
      (node (ref "R261") (pin "1") (pinfunction "1_1") (pintype "passive"))
      (node (ref "U3") (pin "B15") (pinfunction "PA12_B15") (pintype "passive"))
    )
    (net (code "61") (name "/PA13") (class "Default")
      (node (ref "U3") (pin "A15") (pinfunction "PA13_A15") (pintype "passive"))
    )
    (net (code "62") (name "/PA14") (class "Default")
      (node (ref "U3") (pin "A14") (pinfunction "PA14_A14") (pintype "passive"))
    )
    (net (code "63") (name "/PA15") (class "Default")
      (node (ref "U3") (pin "A13") (pinfunction "PA15_A13") (pintype "passive"))
    )
    (net (code "64") (name "/PAR_D7") (class "Default")
      (node (ref "R114") (pin "1") (pinfunction "1_1") (pintype "passive"))
    )
    (net (code "67") (name "/PB0") (class "Default")
      (node (ref "R282") (pin "2") (pinfunction "2_2") (pintype "passive"))
      (node (ref "U3") (pin "R5") (pinfunction "PB0_R5") (pintype "passive"))
    )
    (net (code "68") (name "/PB1") (class "Default")
      (node (ref "R234") (pin "2") (pinfunction "2_2") (pintype "passive"))
      (node (ref "U3") (pin "R4") (pinfunction "PB1_R4") (pintype "passive"))
    )
    (net (code "69") (name "/PB2") (class "Default")
      (node (ref "R5") (pin "2") (pinfunction "2_2") (pintype "passive"))
      (node (ref "U3") (pin "M5") (pinfunction "PB2_M5") (pintype "passive"))
    )
    (net (code "70") (name "/PB3") (class "Default")
      (node (ref "JP4") (pin "2") (pintype "passive"))
      (node (ref "U3") (pin "A10") (pinfunction "PB3_A10") (pintype "passive"))
    )
    (net (code "71") (name "/PB4") (class "Default")
      (node (ref "U3") (pin "A9") (pinfunction "PB4_A9") (pintype "passive"))
    )
    (net (code "72") (name "/PB5") (class "Default")
      (node (ref "U3") (pin "A8") (pinfunction "PB5_A8") (pintype "passive"))
    )
    (net (code "73") (name "/PB6") (class "Default")
      (node (ref "U3") (pin "B6") (pinfunction "PB6_B6") (pintype "passive"))
    )
    (net (code "74") (name "/PB7") (class "Default")
      (node (ref "U3") (pin "B5") (pinfunction "PB7_B5") (pintype "passive"))
    )
    (net (code "75") (name "/PB8") (class "Default")
      (node (ref "R240") (pin "2") (pinfunction "2_2") (pintype "passive"))
      (node (ref "R243") (pin "2") (pinfunction "2_2") (pintype "passive"))
      (node (ref "U3") (pin "A7") (pinfunction "PB8_A7") (pintype "passive"))
    )
    (net (code "76") (name "/PB9") (class "Default")
      (node (ref "U3") (pin "B4") (pinfunction "PB9_B4") (pintype "passive"))
    )
    (net (code "77") (name "/PB10") (class "Default")
      (node (ref "U3") (pin "P12") (pinfunction "PB10_P12") (pintype "passive"))
    )
    (net (code "78") (name "/PB11") (class "Default")
      (node (ref "U3") (pin "R13") (pinfunction "PB11_R13") (pintype "passive"))
    )
    (net (code "79") (name "/PB12") (class "Default")
      (node (ref "R260") (pin "2") (pinfunction "2_2") (pintype "passive"))
      (node (ref "U3") (pin "L13") (pinfunction "PB12_L13") (pintype "passive"))
    )
    (net (code "80") (name "/PB13") (class "Default")
      (node (ref "R264") (pin "2") (pinfunction "2_2") (pintype "passive"))
      (node (ref "U3") (pin "K14") (pinfunction "PB13_K14") (pintype "passive"))
    )
    (net (code "81") (name "/PB14") (class "Default")
      (node (ref "U3") (pin "R14") (pinfunction "PB14_R14") (pintype "passive"))
    )
    (net (code "82") (name "/PB15") (class "Default")
      (node (ref "U3") (pin "R15") (pinfunction "PB15_R15") (pintype "passive"))
    )
    (net (code "84") (name "/PC0") (class "Default")
      (node (ref "U3") (pin "M2") (pinfunction "PC0_M2") (pintype "passive"))
    )
    (net (code "85") (name "/PC1") (class "Default")
      (node (ref "R218") (pin "2") (pinfunction "2_2") (pintype "passive"))
      (node (ref "R222") (pin "2") (pinfunction "2_2") (pintype "passive"))
      (node (ref "U3") (pin "M3") (pinfunction "PC1_M3") (pintype "passive"))
    )
    (net (code "86") (name "/PC2") (class "Default")
      (node (ref "R228") (pin "2") (pinfunction "2_2") (pintype "passive"))
      (node (ref "R232") (pin "2") (pinfunction "2_2") (pintype "passive"))
      (node (ref "U3") (pin "M4") (pinfunction "PC2_M4") (pintype "passive"))
    )
    (net (code "87") (name "/PC3") (class "Default")
      (node (ref "R238") (pin "2") (pinfunction "2_2") (pintype "passive"))
      (node (ref "R242") (pin "2") (pinfunction "2_2") (pintype "passive"))
      (node (ref "U3") (pin "L4") (pinfunction "PC3_L4") (pintype "passive"))
    )
    (net (code "88") (name "/PC4") (class "Default")
      (node (ref "R235") (pin "2") (pinfunction "2_2") (pintype "passive"))
      (node (ref "R239") (pin "2") (pinfunction "2_2") (pintype "passive"))
      (node (ref "U3") (pin "N5") (pinfunction "PC4_N5") (pintype "passive"))
    )
    (net (code "89") (name "/PC5") (class "Default")
      (node (ref "R263") (pin "2") (pinfunction "2_2") (pintype "passive"))
      (node (ref "R267") (pin "2") (pinfunction "2_2") (pintype "passive"))
      (node (ref "U3") (pin "P5") (pinfunction "PC5_P5") (pintype "passive"))
    )
    (net (code "90") (name "/PC6") (class "Default")
      (node (ref "JP4") (pin "3") (pintype "passive"))
      (node (ref "R292") (pin "2") (pinfunction "2_2") (pintype "passive"))
      (node (ref "U3") (pin "H15") (pinfunction "PC6_H15") (pintype "passive"))
    )
    (net (code "91") (name "/PC7") (class "Default")
      (node (ref "R45") (pin "1") (pinfunction "1_1") (pintype "passive"))
      (node (ref "U3") (pin "G15") (pinfunction "PC7_G15") (pintype "passive"))
    )
    (net (code "92") (name "/PC8") (class "Default")
      (node (ref "R280") (pin "2") (pinfunction "2_2") (pintype "passive"))
      (node (ref "R281") (pin "2") (pinfunction "2_2") (pintype "passive"))
      (node (ref "U3") (pin "G14") (pinfunction "PC8_G14") (pintype "passive"))
    )
    (net (code "93") (name "/PC9") (class "Default")
      (node (ref "R265") (pin "2") (pinfunction "2_2") (pintype "passive"))
      (node (ref "U3") (pin "F14") (pinfunction "PC9_F14") (pintype "passive"))
    )
    (net (code "94") (name "/PC10") (class "Default")
      (node (ref "R293") (pin "2") (pinfunction "2_2") (pintype "passive"))
      (node (ref "U3") (pin "B14") (pinfunction "PC10_B14") (pintype "passive"))
    )
    (net (code "95") (name "/PC11") (class "Default")
      (node (ref "R284") (pin "2") (pinfunction "2_2") (pintype "passive"))
      (node (ref "U3") (pin "B13") (pinfunction "PC11_B13") (pintype "passive"))
    )
    (net (code "96") (name "/PC12") (class "Default")
      (node (ref "U3") (pin "A12") (pinfunction "PC12_A12") (pintype "passive"))
    )
    (net (code "97") (name "/PC13") (class "Default")
      (node (ref "U3") (pin "D1") (pinfunction "PC13-ANTI_TAMP_D1") (pintype "passive"))
    )
    (net (code "98") (name "/PC14") (class "Default")
      (node (ref "R19") (pin "2") (pinfunction "2_2") (pintype "passive"))
      (node (ref "U3") (pin "E1") (pinfunction "PC14-OSC32_IN_E1") (pintype "passive"))
    )
    (net (code "99") (name "/PC15") (class "Default")
      (node (ref "R18") (pin "2") (pinfunction "2_2") (pintype "passive"))
      (node (ref "U3") (pin "F1") (pinfunction "PC15-OSC32_OUT_F1") (pintype "passive"))
    )
    (net (code "101") (name "/PD0") (class "Default")
      (node (ref "R274") (pin "2") (pinfunction "2_2") (pintype "passive"))
    )
    (net (code "102") (name "/PD1") (class "Default")
      (node (ref "R288") (pin "2") (pinfunction "2_2") (pintype "passive"))
    )
    (net (code "103") (name "/PD2") (class "Default")
      (node (ref "R294") (pin "2") (pinfunction "2_2") (pintype "passive"))
      (node (ref "U3") (pin "D12") (pinfunction "PD2_D12") (pintype "passive"))
    )
    (net (code "104") (name "/PD3") (class "Default")
      (node (ref "U3") (pin "C11") (pinfunction "PD3_C11") (pintype "passive"))
    )
    (net (code "105") (name "/PD4") (class "Default")
      (node (ref "U3") (pin "D11") (pinfunction "PD4_D11") (pintype "passive"))
    )
    (net (code "106") (name "/PD5") (class "Default")
      (node (ref "U3") (pin "C10") (pinfunction "PD5_C10") (pintype "passive"))
    )
    (net (code "107") (name "/PD6") (class "Default")
      (node (ref "JP5") (pin "2") (pintype "passive"))
      (node (ref "U3") (pin "B11") (pinfunction "PD6_B11") (pintype "passive"))
    )
    (net (code "108") (name "/PD7") (class "Default")
      (node (ref "U3") (pin "A11") (pinfunction "PD7_A11") (pintype "passive"))
    )
    (net (code "109") (name "/PD8") (class "Default")
      (node (ref "R60") (pin "2") (pinfunction "2_2") (pintype "passive"))
    )
    (net (code "110") (name "/PD9") (class "Default")
      (node (ref "R72") (pin "2") (pinfunction "2_2") (pintype "passive"))
    )
    (net (code "111") (name "/PD10") (class "Default")
      (node (ref "R73") (pin "2") (pinfunction "2_2") (pintype "passive"))
    )
    (net (code "112") (name "/PD11") (class "Default")
      (node (ref "R272") (pin "1") (pinfunction "1_1") (pintype "passive"))
    )
    (net (code "113") (name "/PD12") (class "Default")
      (node (ref "R287") (pin "2") (pinfunction "2_2") (pintype "passive"))
    )
    (net (code "114") (name "/PD13") (class "Default")
      (node (ref "R270") (pin "2") (pinfunction "2_2") (pintype "passive"))
    )
    (net (code "115") (name "/PD14") (class "Default")
      (node (ref "R74") (pin "2") (pinfunction "2_2") (pintype "passive"))
    )
    (net (code "116") (name "/PD15") (class "Default")
      (node (ref "R61") (pin "2") (pinfunction "2_2") (pintype "passive"))
    )
    (net (code "118") (name "/PE0") (class "Default")
      (node (ref "U3") (pin "A6") (pinfunction "PE0_A6") (pintype "passive"))
    )
    (net (code "119") (name "/PE1") (class "Default")
      (node (ref "U3") (pin "A5") (pinfunction "PE1_A5") (pintype "passive"))
    )
    (net (code "120") (name "/PE2") (class "Default")
      (node (ref "R40") (pin "2") (pinfunction "2_2") (pintype "passive"))
      (node (ref "R41") (pin "2") (pinfunction "2_2") (pintype "passive"))
    )
    (net (code "121") (name "/PE3") (class "Default")
      (node (ref "R36") (pin "2") (pinfunction "2_2") (pintype "passive"))
      (node (ref "R37") (pin "2") (pinfunction "2_2") (pintype "passive"))
    )
    (net (code "122") (name "/PE4") (class "Default")
      (node (ref "R34") (pin "2") (pinfunction "2_2") (pintype "passive"))
      (node (ref "R35") (pin "2") (pinfunction "2_2") (pintype "passive"))
    )
    (net (code "123") (name "/PE5") (class "Default")
      (node (ref "R24") (pin "2") (pinfunction "2_2") (pintype "passive"))
      (node (ref "R29") (pin "2") (pinfunction "2_2") (pintype "passive"))
    )
    (net (code "124") (name "/PE6") (class "Default")
      (node (ref "R30") (pin "2") (pinfunction "2_2") (pintype "passive"))
      (node (ref "R32") (pin "2") (pinfunction "2_2") (pintype "passive"))
    )
    (net (code "125") (name "/PE7") (class "Default")
      (node (ref "R65") (pin "2") (pinfunction "2_2") (pintype "passive"))
    )
    (net (code "126") (name "/PE8") (class "Default")
      (node (ref "R54") (pin "2") (pinfunction "2_2") (pintype "passive"))
    )
    (net (code "127") (name "/PE9") (class "Default")
      (node (ref "R53") (pin "2") (pinfunction "2_2") (pintype "passive"))
    )
    (net (code "128") (name "/PE10") (class "Default")
      (node (ref "R66") (pin "2") (pinfunction "2_2") (pintype "passive"))
    )
    (net (code "129") (name "/PE11") (class "Default")
      (node (ref "R55") (pin "2") (pinfunction "2_2") (pintype "passive"))
    )
    (net (code "130") (name "/PE12") (class "Default")
      (node (ref "R67") (pin "2") (pinfunction "2_2") (pintype "passive"))
    )
    (net (code "131") (name "/PE13") (class "Default")
      (node (ref "R69") (pin "2") (pinfunction "2_2") (pintype "passive"))
    )
    (net (code "132") (name "/PE14") (class "Default")
      (node (ref "R56") (pin "2") (pinfunction "2_2") (pintype "passive"))
    )
    (net (code "133") (name "/PE15") (class "Default")
      (node (ref "R68") (pin "2") (pinfunction "2_2") (pintype "passive"))
    )
    (net (code "135") (name "/PF0") (class "Default")
      (node (ref "R231") (pin "2") (pinfunction "2_2") (pintype "passive"))
    )
    (net (code "136") (name "/PF1") (class "Default")
      (node (ref "R226") (pin "2") (pinfunction "2_2") (pintype "passive"))
    )
    (net (code "137") (name "/PF2") (class "Default")
      (node (ref "R224") (pin "2") (pinfunction "2_2") (pintype "passive"))
    )
    (net (code "138") (name "/PF3") (class "Default")
      (node (ref "R221") (pin "2") (pinfunction "2_2") (pintype "passive"))
    )
    (net (code "139") (name "/PF4") (class "Default")
      (node (ref "R217") (pin "2") (pinfunction "2_2") (pintype "passive"))
    )
    (net (code "140") (name "/PF5") (class "Default")
      (node (ref "R213") (pin "2") (pinfunction "2_2") (pintype "passive"))
    )
    (net (code "141") (name "/PF6") (class "Default")
      (node (ref "U3") (pin "K2") (pinfunction "PF6_K2") (pintype "passive"))
    )
    (net (code "142") (name "/PF7") (class "Default")
      (node (ref "U3") (pin "K1") (pinfunction "PF7_K1") (pintype "passive"))
    )
    (net (code "143") (name "/PF8") (class "Default")
      (node (ref "U3") (pin "L3") (pinfunction "PF8_L3") (pintype "passive"))
    )
    (net (code "144") (name "/PF9") (class "Default")
      (node (ref "U3") (pin "L2") (pinfunction "PF9_L2") (pintype "passive"))
    )
    (net (code "145") (name "/PF10") (class "Default")
      (node (ref "U3") (pin "L1") (pinfunction "PF10_L1") (pintype "passive"))
    )
    (net (code "146") (name "/PF11") (class "Default")
      (node (ref "R52") (pin "2") (pinfunction "2_2") (pintype "passive"))
    )
    (net (code "147") (name "/PF12") (class "Default")
      (node (ref "R253") (pin "2") (pinfunction "2_2") (pintype "passive"))
    )
    (net (code "148") (name "/PF13") (class "Default")
      (node (ref "R250") (pin "2") (pinfunction "2_2") (pintype "passive"))
    )
    (net (code "149") (name "/PF14") (class "Default")
      (node (ref "R254") (pin "2") (pinfunction "2_2") (pintype "passive"))
    )
    (net (code "150") (name "/PF15") (class "Default")
      (node (ref "R273") (pin "2") (pinfunction "2_2") (pintype "passive"))
    )
    (net (code "152") (name "/PG0") (class "Default")
      (node (ref "R258") (pin "2") (pinfunction "2_2") (pintype "passive"))
    )
    (net (code "153") (name "/PG1") (class "Default")
      (node (ref "R257") (pin "2") (pinfunction "2_2") (pintype "passive"))
    )
    (net (code "154") (name "/PG2") (class "Default")
      (node (ref "R285") (pin "2") (pinfunction "2_2") (pintype "passive"))
    )
    (net (code "155") (name "/PG3") (class "Default")
      (node (ref "R269") (pin "2") (pinfunction "2_2") (pintype "passive"))
    )
    (net (code "156") (name "/PG4") (class "Default")
      (node (ref "R286") (pin "2") (pinfunction "2_2") (pintype "passive"))
    )
    (net (code "157") (name "/PG5") (class "Default")
      (node (ref "R271") (pin "2") (pinfunction "2_2") (pintype "passive"))
    )
    (net (code "158") (name "/PG6") (class "Default")
      (node (ref "U3") (pin "J15") (pinfunction "PG6_J15") (pintype "passive"))
    )
    (net (code "159") (name "/PG7") (class "Default")
      (node (ref "U3") (pin "J14") (pinfunction "PG7_J14") (pintype "passive"))
    )
    (net (code "160") (name "/PG8") (class "Default")
      (node (ref "R62") (pin "2") (pinfunction "2_2") (pintype "passive"))
    )
    (net (code "161") (name "/PG9") (class "Default")
      (node (ref "U3") (pin "D9") (pinfunction "PG9_D9") (pintype "passive"))
    )
    (net (code "162") (name "/PG10") (class "Default")
      (node (ref "U3") (pin "C8") (pinfunction "PG10_C8") (pintype "passive"))
    )
    (net (code "163") (name "/PG11") (class "Default")
      (node (ref "R246") (pin "1") (pinfunction "1_1") (pintype "passive"))
      (node (ref "R249") (pin "1") (pinfunction "1_1") (pintype "passive"))
      (node (ref "U3") (pin "B8") (pinfunction "PG11_B8") (pintype "passive"))
    )
    (net (code "164") (name "/PG12") (class "Default")
      (node (ref "U3") (pin "C7") (pinfunction "PG12_C7") (pintype "passive"))
    )
    (net (code "165") (name "/PG13") (class "Default")
      (node (ref "R233") (pin "1") (pinfunction "1_1") (pintype "passive"))
      (node (ref "U3") (pin "B3") (pinfunction "PG13_B3") (pintype "passive"))
    )
    (net (code "166") (name "/PG14") (class "Default")
      (node (ref "R236") (pin "1") (pinfunction "1_1") (pintype "passive"))
      (node (ref "U3") (pin "A4") (pinfunction "PG14_A4") (pintype "passive"))
    )
    (net (code "167") (name "/PG15") (class "Default")
      (node (ref "R42") (pin "2") (pinfunction "2_2") (pintype "passive"))
    )
    (net (code "169") (name "/PH0") (class "Default")
      (node (ref "R20") (pin "1") (pinfunction "1_1") (pintype "passive"))
      (node (ref "U3") (pin "G1") (pinfunction "PH0-OSC_IN_G1") (pintype "passive"))
    )
    (net (code "170") (name "/PH1") (class "Default")
      (node (ref "C23") (pin "1") (pinfunction "1_1") (pintype "passive"))
      (node (ref "U3") (pin "H1") (pinfunction "PH1-OSC_OUT_H1") (pintype "passive"))
      (node (ref "X2") (pin "1") (pinfunction "1_1") (pintype "passive"))
    )
    (net (code "171") (name "/PH2") (class "Default")
      (node (ref "U3") (pin "K4") (pinfunction "PH2_K4") (pintype "passive"))
    )
    (net (code "172") (name "/PH3") (class "Default")
      (node (ref "R248") (pin "1") (pinfunction "1_1") (pintype "passive"))
    )
    (net (code "173") (name "/PH4") (class "Default")
      (node (ref "U3") (pin "H4") (pinfunction "PH4_H4") (pintype "passive"))
    )
    (net (code "174") (name "/PH5") (class "Default")
      (node (ref "R251") (pin "1") (pinfunction "1_1") (pintype "passive"))
    )
    (net (code "175") (name "/PH6") (class "Default")
      (node (ref "U3") (pin "P13") (pinfunction "PH6_P13") (pintype "passive"))
    )
    (net (code "176") (name "/PH7") (class "Default")
      (node (ref "U3") (pin "N13") (pinfunction "PH7_N13") (pintype "passive"))
    )
    (net (code "177") (name "/PH8") (class "Default")
      (node (ref "R57") (pin "1") (pinfunction "1_1") (pintype "passive"))
    )
    (net (code "178") (name "/PH9") (class "Default")
      (node (ref "R58") (pin "1") (pinfunction "1_1") (pintype "passive"))
    )
    (net (code "179") (name "/PH10") (class "Default")
      (node (ref "R70") (pin "1") (pinfunction "1_1") (pintype "passive"))
    )
    (net (code "180") (name "/PH11") (class "Default")
      (node (ref "R71") (pin "1") (pinfunction "1_1") (pintype "passive"))
    )
    (net (code "181") (name "/PH12") (class "Default")
      (node (ref "R59") (pin "1") (pinfunction "1_1") (pintype "passive"))
    )
    (net (code "182") (name "/PH13") (class "Default")
      (node (ref "R278") (pin "1") (pinfunction "1_1") (pintype "passive"))
    )
    (net (code "183") (name "/PH14") (class "Default")
      (node (ref "R291") (pin "1") (pinfunction "1_1") (pintype "passive"))
    )
    (net (code "184") (name "/PH15") (class "Default")
      (node (ref "R290") (pin "1") (pinfunction "1_1") (pintype "passive"))
    )
    (net (code "186") (name "/PI0") (class "Default")
      (node (ref "R277") (pin "1") (pinfunction "1_1") (pintype "passive"))
    )
    (net (code "187") (name "/PI1") (class "Default")
      (node (ref "R276") (pin "1") (pinfunction "1_1") (pintype "passive"))
    )
    (net (code "188") (name "/PI2") (class "Default")
      (node (ref "R275") (pin "1") (pinfunction "1_1") (pintype "passive"))
    )
    (net (code "189") (name "/PI3") (class "Default")
      (node (ref "R289") (pin "1") (pinfunction "1_1") (pintype "passive"))
    )
    (net (code "190") (name "/PI4") (class "Default")
      (node (ref "U3") (pin "C3") (pinfunction "PI4_C3") (pintype "passive"))
    )
    (net (code "191") (name "/PI5") (class "Default")
      (node (ref "U3") (pin "D3") (pinfunction "PI5_D3") (pintype "passive"))
    )
    (net (code "192") (name "/PI6") (class "Default")
      (node (ref "R247") (pin "1") (pinfunction "1_1") (pintype "passive"))
    )
    (net (code "193") (name "/PI7") (class "Default")
      (node (ref "R237") (pin "1") (pinfunction "1_1") (pintype "passive"))
    )
    (net (code "194") (name "/PI8") (class "Default")
      (node (ref "U3") (pin "C2") (pinfunction "PI8-ANTI_TAMP2_C2") (pintype "passive"))
    )
    (net (code "195") (name "/PI9") (class "Default")
      (node (ref "R241") (pin "1") (pinfunction "1_1") (pintype "passive"))
    )
    (net (code "196") (name "/PI10") (class "Default")
      (node (ref "R244") (pin "1") (pinfunction "1_1") (pintype "passive"))
    )
    (net (code "197") (name "/PI11") (class "Default")
      (node (ref "U3") (pin "F3") (pinfunction "PI11_F3") (pintype "passive"))
    )
    (net (code "198") (name "/PI12") (class "Default")
      (node (ref "U3") (pin "E3") (pinfunction "PI12_E3") (pintype "passive"))
    )
    (net (code "199") (name "/PI13") (class "Default")
      (node (ref "U3") (pin "G3") (pinfunction "PI13_G3") (pintype "passive"))
    )
    (net (code "200") (name "/PI14") (class "Default")
      (node (ref "R295") (pin "1") (pinfunction "1_1") (pintype "passive"))
    )
    (net (code "201") (name "/PI15") (class "Default")
      (node (ref "U3") (pin "G4") (pinfunction "PI15_G4") (pintype "passive"))
    )
    (net (code "203") (name "/PJ0") (class "Default")
      (node (ref "U3") (pin "R6") (pinfunction "PJ0_R6") (pintype "passive"))
    )
    (net (code "204") (name "/PJ1") (class "Default")
      (node (ref "U3") (pin "R7") (pinfunction "PJ1_R7") (pintype "passive"))
    )
    (net (code "205") (name "/PJ2") (class "Default")
      (node (ref "U3") (pin "P7") (pinfunction "PJ2_P7") (pintype "passive"))
    )
    (net (code "206") (name "/PJ3") (class "Default")
      (node (ref "U3") (pin "N8") (pinfunction "PJ3_N8") (pintype "passive"))
    )
    (net (code "207") (name "/PJ4") (class "Default")
      (node (ref "U3") (pin "M9") (pinfunction "PJ4_M9") (pintype "passive"))
    )
    (net (code "208") (name "/PJ5") (class "Default")
      (node (ref "U3") (pin "M14") (pinfunction "PJ5_M14") (pintype "passive"))
    )
    (net (code "209") (name "/PJ6") (class "Default")
      (node (ref "U3") (pin "K12") (pinfunction "PJ6_K12") (pintype "passive"))
    )
    (net (code "210") (name "/PJ7") (class "Default")
      (node (ref "U3") (pin "J12") (pinfunction "PJ7_J12") (pintype "passive"))
    )
    (net (code "211") (name "/PJ8") (class "Default")
      (node (ref "U3") (pin "H12") (pinfunction "PJ8_H12") (pintype "passive"))
    )
    (net (code "212") (name "/PJ9") (class "Default")
      (node (ref "U3") (pin "J13") (pinfunction "PJ9_J13") (pintype "passive"))
    )
    (net (code "213") (name "/PJ10") (class "Default")
      (node (ref "U3") (pin "H13") (pinfunction "PJ10_H13") (pintype "passive"))
    )
    (net (code "214") (name "/PJ11") (class "Default")
      (node (ref "U3") (pin "G12") (pinfunction "PJ11_G12") (pintype "passive"))
    )
    (net (code "215") (name "/PJ12") (class "Default")
      (node (ref "U3") (pin "B10") (pinfunction "PJ12_B10") (pintype "passive"))
    )
    (net (code "216") (name "/PJ13") (class "Default")
      (node (ref "U3") (pin "B9") (pinfunction "PJ13_B9") (pintype "passive"))
    )
    (net (code "217") (name "/PJ14") (class "Default")
      (node (ref "U3") (pin "C9") (pinfunction "PJ14_C9") (pintype "passive"))
    )
    (net (code "218") (name "/PJ15") (class "Default")
      (node (ref "U3") (pin "D10") (pinfunction "PJ15_D10") (pintype "passive"))
    )
    (net (code "220") (name "/PK0") (class "Default")
      (node (ref "U3") (pin "G13") (pinfunction "PK0_G13") (pintype "passive"))
    )
    (net (code "221") (name "/PK1") (class "Default")
      (node (ref "U3") (pin "F12") (pinfunction "PK1_F12") (pintype "passive"))
    )
    (net (code "222") (name "/PK2") (class "Default")
      (node (ref "U3") (pin "F13") (pinfunction "PK2_F13") (pintype "passive"))
    )
    (net (code "223") (name "/PK3") (class "Default")
      (node (ref "U3") (pin "D8") (pinfunction "PK3_D8") (pintype "passive"))
    )
    (net (code "224") (name "/PK4") (class "Default")
      (node (ref "U3") (pin "D7") (pinfunction "PK4_D7") (pintype "passive"))
    )
    (net (code "225") (name "/PK5") (class "Default")
      (node (ref "U3") (pin "C6") (pinfunction "PK5_C6") (pintype "passive"))
    )
    (net (code "226") (name "/PK6") (class "Default")
      (node (ref "U3") (pin "C5") (pinfunction "PK6_C5") (pintype "passive"))
    )
    (net (code "227") (name "/PK7") (class "Default")
      (node (ref "U3") (pin "C4") (pinfunction "PK7_C4") (pintype "passive"))
    )
    (net (code "229") (name "/RESET#") (class "Default")
      (node (ref "B1") (pin "2") (pinfunction "B0_2") (pintype "passive"))
      (node (ref "B1") (pin "3") (pinfunction "B1_3") (pintype "passive"))
      (node (ref "C91") (pin "2") (pinfunction "2_2") (pintype "passive"))
      (node (ref "U3") (pin "J1") (pinfunction "NRST_J1") (pintype "passive"))
    )
    (net (code "230") (name "/RS232{slash}IrDA_TX") (class "Default")
      (node (ref "R262") (pin "2") (pinfunction "2_2") (pintype "passive"))
    )
    (net (code "231") (name "/SAI1_SDA") (class "Default")
      (node (ref "R120") (pin "2") (pinfunction "2_2") (pintype "passive"))
    )
    (net (code "232") (name "/TDO{slash}SWO") (class "Default")
      (node (ref "JP4") (pin "1") (pintype "passive"))
    )
    (net (code "233") (name "/TRACE_CK") (class "Default")
      (node (ref "R38") (pin "1") (pinfunction "1_1") (pintype "passive"))
    )
    (net (code "234") (name "/TRACE_D0") (class "Default")
      (node (ref "R39") (pin "1") (pinfunction "1_1") (pintype "passive"))
    )
    (net (code "235") (name "/TRACE_D1") (class "Default")
      (node (ref "R33") (pin "1") (pinfunction "1_1") (pintype "passive"))
    )
    (net (code "236") (name "/TRACE_D2") (class "Default")
      (node (ref "R23") (pin "1") (pinfunction "1_1") (pintype "passive"))
    )
    (net (code "237") (name "/TRACE_D3") (class "Default")
      (node (ref "R128") (pin "1") (pinfunction "1_1") (pintype "passive"))
    )
    (net (code "239") (name "/USB_FS1_DP") (class "Default")
      (node (ref "R261") (pin "2") (pinfunction "2_2") (pintype "passive"))
    )
    (net (code "240") (name "/USB_FS2_ID") (class "Default")
      (node (ref "R260") (pin "1") (pinfunction "1_1") (pintype "passive"))
    )
    (net (code "241") (name "/WAKEUP") (class "Default")
      (node (ref "R219") (pin "2") (pinfunction "2_2") (pintype "passive"))
    )
    (net (code "242") (name "/uSD_CMD") (class "Default")
      (node (ref "R294") (pin "1") (pinfunction "1_1") (pintype "passive"))
    )
    (net (code "243") (name "/uSD_D0") (class "Default")
      (node (ref "R281") (pin "1") (pinfunction "1_1") (pintype "passive"))
    )
    (net (code "244") (name "/uSD_D1") (class "Default")
      (node (ref "R265") (pin "1") (pinfunction "1_1") (pintype "passive"))
    )
    (net (code "245") (name "/uSD_D2") (class "Default")
      (node (ref "R293") (pin "1") (pinfunction "1_1") (pintype "passive"))
    )
    (net (code "246") (name "/uSD_D3") (class "Default")
      (node (ref "R284") (pin "1") (pinfunction "1_1") (pintype "passive"))
    )
    (net (code "247") (name "GND") (class "Default")
      (node (ref "B1") (pin "1") (pinfunction "A0_1") (pintype "passive"))
      (node (ref "B1") (pin "4") (pinfunction "A1_4") (pintype "passive"))
      (node (ref "BT1") (pin "2") (pinfunction "-_2") (pintype "passive"))
      (node (ref "C103") (pin "2") (pinfunction "2_2") (pintype "passive"))
      (node (ref "C104") (pin "2") (pinfunction "2_2") (pintype "passive"))
      (node (ref "C105") (pin "2") (pinfunction "2_2") (pintype "passive"))
      (node (ref "C106") (pin "2") (pinfunction "2_2") (pintype "passive"))
      (node (ref "C107") (pin "1") (pinfunction "1_1") (pintype "passive"))
      (node (ref "C108") (pin "2") (pinfunction "2_2") (pintype "passive"))
      (node (ref "C109") (pin "2") (pinfunction "2_2") (pintype "passive"))
      (node (ref "C110") (pin "1") (pinfunction "1_1") (pintype "passive"))
      (node (ref "C111") (pin "2") (pinfunction "2_2") (pintype "passive"))
      (node (ref "C112") (pin "2") (pinfunction "2_2") (pintype "passive"))
      (node (ref "C113") (pin "2") (pinfunction "2_2") (pintype "passive"))
      (node (ref "C114") (pin "2") (pinfunction "2_2") (pintype "passive"))
      (node (ref "C115") (pin "2") (pinfunction "2_2") (pintype "passive"))
      (node (ref "C118") (pin "2") (pinfunction "2_2") (pintype "passive"))
      (node (ref "C119") (pin "2") (pinfunction "2_2") (pintype "passive"))
      (node (ref "C120") (pin "2") (pinfunction "2_2") (pintype "passive"))
      (node (ref "C121") (pin "2") (pinfunction "2_2") (pintype "passive"))
      (node (ref "C122") (pin "2") (pinfunction "2_2") (pintype "passive"))
      (node (ref "C123") (pin "2") (pinfunction "2_2") (pintype "passive"))
      (node (ref "C125") (pin "2") (pinfunction "2_2") (pintype "passive"))
      (node (ref "C126") (pin "2") (pinfunction "2_2") (pintype "passive"))
      (node (ref "C127") (pin "2") (pinfunction "2_2") (pintype "passive"))
      (node (ref "C128") (pin "2") (pinfunction "2_2") (pintype "passive"))
      (node (ref "C129") (pin "2") (pinfunction "2_2") (pintype "passive"))
      (node (ref "C130") (pin "2") (pinfunction "2_2") (pintype "passive"))
      (node (ref "C133") (pin "2") (pinfunction "2_2") (pintype "passive"))
      (node (ref "C20") (pin "2") (pinfunction "2_2") (pintype "passive"))
      (node (ref "C21") (pin "2") (pinfunction "2_2") (pintype "passive"))
      (node (ref "C22") (pin "2") (pinfunction "2_2") (pintype "passive"))
      (node (ref "C23") (pin "2") (pinfunction "2_2") (pintype "passive"))
      (node (ref "C32") (pin "2") (pinfunction "2_2") (pintype "passive"))
      (node (ref "C91") (pin "1") (pinfunction "1_1") (pintype "passive"))
      (node (ref "R21") (pin "2") (pinfunction "2_2") (pintype "passive"))
      (node (ref "R24") (pin "1") (pinfunction "1_1") (pintype "passive"))
      (node (ref "R245") (pin "1") (pinfunction "1_1") (pintype "passive"))
      (node (ref "R30") (pin "1") (pinfunction "1_1") (pintype "passive"))
      (node (ref "R35") (pin "1") (pinfunction "1_1") (pintype "passive"))
      (node (ref "R37") (pin "1") (pinfunction "1_1") (pintype "passive"))
      (node (ref "R41") (pin "1") (pinfunction "1_1") (pintype "passive"))
      (node (ref "SW1") (pin "3") (pintype "passive"))
      (node (ref "SW2") (pin "3") (pintype "passive"))
      (node (ref "U3") (pin "F10") (pinfunction "VSS2_F10") (pintype "passive"))
      (node (ref "U3") (pin "F2") (pinfunction "VSS13-VSS18_F2") (pintype "passive"))
      (node (ref "U3") (pin "F6") (pinfunction "VSS3_F6") (pintype "passive"))
      (node (ref "U3") (pin "F7") (pinfunction "VSS11_F7") (pintype "passive"))
      (node (ref "U3") (pin "F8") (pinfunction "VSS10_F8") (pintype "passive"))
      (node (ref "U3") (pin "F9") (pinfunction "VSS15_F9") (pintype "passive"))
      (node (ref "U3") (pin "G10") (pinfunction "VSS9_G10") (pintype "passive"))
      (node (ref "U3") (pin "G6") (pinfunction "VSS17_G6") (pintype "passive"))
      (node (ref "U3") (pin "H10") (pinfunction "VSS20_H10") (pintype "passive"))
      (node (ref "U3") (pin "H6") (pinfunction "VSS5_H6") (pintype "passive"))
      (node (ref "U3") (pin "J10") (pinfunction "VSS8_J10") (pintype "passive"))
      (node (ref "U3") (pin "J6") (pinfunction "VSS12_J6") (pintype "passive"))
      (node (ref "U3") (pin "K10") (pinfunction "VSS14_K10") (pintype "passive"))
      (node (ref "U3") (pin "K6") (pinfunction "VSS4_K6") (pintype "passive"))
      (node (ref "U3") (pin "K7") (pinfunction "VSS6_K7") (pintype "passive"))
      (node (ref "U3") (pin "K8") (pinfunction "VSS7_K8") (pintype "passive"))
      (node (ref "U3") (pin "K9") (pinfunction "VSS1_K9") (pintype "passive"))
      (node (ref "U3") (pin "L6") (pinfunction "VSS19_L6") (pintype "passive"))
      (node (ref "U3") (pin "M1") (pinfunction "VSSA_M1") (pintype "passive"))
      (node (ref "U3") (pin "N1") (pinfunction "VREF-_N1") (pintype "passive"))
    )
    (net (code "248") (name "Net-(BT1-+)") (class "Default")
      (node (ref "BT1") (pin "1") (pinfunction "+_1") (pintype "passive"))
      (node (ref "JP8") (pin "3") (pintype "passive"))
    )
    (net (code "249") (name "Net-(C20-Pad1)") (class "Default")
      (node (ref "C20") (pin "1") (pinfunction "1_1") (pintype "passive"))
      (node (ref "R20") (pin "2") (pinfunction "2_2") (pintype "passive"))
      (node (ref "X2") (pin "2") (pinfunction "2_2") (pintype "passive"))
    )
    (net (code "250") (name "Net-(C21-Pad1)") (class "Default")
      (node (ref "C21") (pin "1") (pinfunction "1_1") (pintype "passive"))
      (node (ref "R18") (pin "1") (pinfunction "1_1") (pintype "passive"))
      (node (ref "X1") (pin "4") (pinfunction "4_4") (pintype "passive"))
    )
    (net (code "251") (name "Net-(C22-Pad1)") (class "Default")
      (node (ref "C22") (pin "1") (pinfunction "1_1") (pintype "passive"))
      (node (ref "R19") (pin "1") (pinfunction "1_1") (pintype "passive"))
      (node (ref "X1") (pin "1") (pinfunction "1_1") (pintype "passive"))
    )
    (net (code "252") (name "Net-(R5-Pad1)") (class "Default")
      (node (ref "R5") (pin "1") (pinfunction "1_1") (pintype "passive"))
      (node (ref "SW2") (pin "2") (pintype "passive"))
    )
    (net (code "253") (name "Net-(U3A-PDR_ON)") (class "Default")
      (node (ref "R21") (pin "1") (pinfunction "1_1") (pintype "passive"))
      (node (ref "R22") (pin "1") (pinfunction "1_1") (pintype "passive"))
      (node (ref "U3") (pin "E5") (pinfunction "PDR_ON_E5") (pintype "passive"))
    )
    (net (code "254") (name "Net-(U3B-PD0)") (class "Default")
      (node (ref "R274") (pin "1") (pinfunction "1_1") (pintype "passive"))
      (node (ref "U3") (pin "B12") (pinfunction "PD0_B12") (pintype "passive"))
    )
    (net (code "255") (name "Net-(U3B-PD1)") (class "Default")
      (node (ref "R288") (pin "1") (pinfunction "1_1") (pintype "passive"))
      (node (ref "U3") (pin "C12") (pinfunction "PD1_C12") (pintype "passive"))
    )
    (net (code "256") (name "Net-(U3B-PD8)") (class "Default")
      (node (ref "R60") (pin "1") (pinfunction "1_1") (pintype "passive"))
      (node (ref "U3") (pin "L15") (pinfunction "PD8_L15") (pintype "passive"))
    )
    (net (code "257") (name "Net-(U3B-PD9)") (class "Default")
      (node (ref "R72") (pin "1") (pinfunction "1_1") (pintype "passive"))
      (node (ref "U3") (pin "L14") (pinfunction "PD9_L14") (pintype "passive"))
    )
    (net (code "258") (name "Net-(U3B-PD10)") (class "Default")
      (node (ref "R73") (pin "1") (pinfunction "1_1") (pintype "passive"))
      (node (ref "U3") (pin "K15") (pinfunction "PD10_K15") (pintype "passive"))
    )
    (net (code "259") (name "Net-(U3B-PD11)") (class "Default")
      (node (ref "R272") (pin "2") (pinfunction "2_2") (pintype "passive"))
      (node (ref "U3") (pin "N10") (pinfunction "PD11_N10") (pintype "passive"))
    )
    (net (code "260") (name "Net-(U3B-PD12)") (class "Default")
      (node (ref "R287") (pin "1") (pinfunction "1_1") (pintype "passive"))
      (node (ref "U3") (pin "M10") (pinfunction "PD12_M10") (pintype "passive"))
    )
    (net (code "261") (name "Net-(U3B-PD13)") (class "Default")
      (node (ref "R270") (pin "1") (pinfunction "1_1") (pintype "passive"))
      (node (ref "U3") (pin "M11") (pinfunction "PD13_M11") (pintype "passive"))
    )
    (net (code "262") (name "Net-(U3B-PD14)") (class "Default")
      (node (ref "R74") (pin "1") (pinfunction "1_1") (pintype "passive"))
      (node (ref "U3") (pin "L12") (pinfunction "PD14_L12") (pintype "passive"))
    )
    (net (code "263") (name "Net-(U3B-PD15)") (class "Default")
      (node (ref "R61") (pin "1") (pinfunction "1_1") (pintype "passive"))
      (node (ref "U3") (pin "K13") (pinfunction "PD15_K13") (pintype "passive"))
    )
    (net (code "264") (name "Net-(U3B-PE2)") (class "Default")
      (node (ref "R38") (pin "2") (pinfunction "2_2") (pintype "passive"))
      (node (ref "R40") (pin "1") (pinfunction "1_1") (pintype "passive"))
      (node (ref "U3") (pin "A3") (pinfunction "PE2_A3") (pintype "passive"))
    )
    (net (code "265") (name "Net-(U3B-PE3)") (class "Default")
      (node (ref "R36") (pin "1") (pinfunction "1_1") (pintype "passive"))
      (node (ref "R39") (pin "2") (pinfunction "2_2") (pintype "passive"))
      (node (ref "U3") (pin "A2") (pinfunction "PE3_A2") (pintype "passive"))
    )
    (net (code "266") (name "Net-(U3B-PE4)") (class "Default")
      (node (ref "R33") (pin "2") (pinfunction "2_2") (pintype "passive"))
      (node (ref "R34") (pin "1") (pinfunction "1_1") (pintype "passive"))
      (node (ref "U3") (pin "A1") (pinfunction "PE4_A1") (pintype "passive"))
    )
    (net (code "267") (name "Net-(U3B-PE5)") (class "Default")
      (node (ref "R23") (pin "2") (pinfunction "2_2") (pintype "passive"))
      (node (ref "R29") (pin "1") (pinfunction "1_1") (pintype "passive"))
      (node (ref "U3") (pin "B1") (pinfunction "PE5_B1") (pintype "passive"))
    )
    (net (code "268") (name "Net-(U3B-PE6)") (class "Default")
      (node (ref "R114") (pin "2") (pinfunction "2_2") (pintype "passive"))
      (node (ref "R120") (pin "1") (pinfunction "1_1") (pintype "passive"))
      (node (ref "R128") (pin "2") (pinfunction "2_2") (pintype "passive"))
      (node (ref "R32") (pin "1") (pinfunction "1_1") (pintype "passive"))
      (node (ref "U3") (pin "B2") (pinfunction "PE6_B2") (pintype "passive"))
    )
    (net (code "269") (name "Net-(U3B-PE7)") (class "Default")
      (node (ref "R65") (pin "1") (pinfunction "1_1") (pintype "passive"))
      (node (ref "U3") (pin "R8") (pinfunction "PE7_R8") (pintype "passive"))
    )
    (net (code "270") (name "Net-(U3B-PE8)") (class "Default")
      (node (ref "R54") (pin "1") (pinfunction "1_1") (pintype "passive"))
      (node (ref "U3") (pin "N9") (pinfunction "PE8_N9") (pintype "passive"))
    )
    (net (code "271") (name "Net-(U3B-PE9)") (class "Default")
      (node (ref "R53") (pin "1") (pinfunction "1_1") (pintype "passive"))
      (node (ref "U3") (pin "P9") (pinfunction "PE9_P9") (pintype "passive"))
    )
    (net (code "272") (name "Net-(U3B-PE10)") (class "Default")
      (node (ref "R66") (pin "1") (pinfunction "1_1") (pintype "passive"))
      (node (ref "U3") (pin "R9") (pinfunction "PE10_R9") (pintype "passive"))
    )
    (net (code "273") (name "Net-(U3B-PE11)") (class "Default")
      (node (ref "R55") (pin "1") (pinfunction "1_1") (pintype "passive"))
      (node (ref "U3") (pin "P10") (pinfunction "PE11_P10") (pintype "passive"))
    )
    (net (code "274") (name "Net-(U3B-PE12)") (class "Default")
      (node (ref "R67") (pin "1") (pinfunction "1_1") (pintype "passive"))
      (node (ref "U3") (pin "R10") (pinfunction "PE12_R10") (pintype "passive"))
    )
    (net (code "275") (name "Net-(U3B-PE13)") (class "Default")
      (node (ref "R69") (pin "1") (pinfunction "1_1") (pintype "passive"))
      (node (ref "U3") (pin "R12") (pinfunction "PE13_R12") (pintype "passive"))
    )
    (net (code "276") (name "Net-(U3B-PE14)") (class "Default")
      (node (ref "R56") (pin "1") (pinfunction "1_1") (pintype "passive"))
      (node (ref "U3") (pin "P11") (pinfunction "PE14_P11") (pintype "passive"))
    )
    (net (code "277") (name "Net-(U3B-PE15)") (class "Default")
      (node (ref "R68") (pin "1") (pinfunction "1_1") (pintype "passive"))
      (node (ref "U3") (pin "R11") (pinfunction "PE15_R11") (pintype "passive"))
    )
    (net (code "278") (name "Net-(U3B-PF0)") (class "Default")
      (node (ref "R231") (pin "1") (pinfunction "1_1") (pintype "passive"))
      (node (ref "U3") (pin "D2") (pinfunction "PF0_D2") (pintype "passive"))
    )
    (net (code "279") (name "Net-(U3B-PF1)") (class "Default")
      (node (ref "R226") (pin "1") (pinfunction "1_1") (pintype "passive"))
      (node (ref "U3") (pin "E2") (pinfunction "PF1_E2") (pintype "passive"))
    )
    (net (code "280") (name "Net-(U3B-PF2)") (class "Default")
      (node (ref "R224") (pin "1") (pinfunction "1_1") (pintype "passive"))
      (node (ref "U3") (pin "G2") (pinfunction "PF2_G2") (pintype "passive"))
    )
    (net (code "281") (name "Net-(U3B-PF3)") (class "Default")
      (node (ref "R221") (pin "1") (pinfunction "1_1") (pintype "passive"))
      (node (ref "U3") (pin "H2") (pinfunction "PF3_H2") (pintype "passive"))
    )
    (net (code "282") (name "Net-(U3B-PF4)") (class "Default")
      (node (ref "R217") (pin "1") (pinfunction "1_1") (pintype "passive"))
      (node (ref "U3") (pin "J2") (pinfunction "PF4_J2") (pintype "passive"))
    )
    (net (code "283") (name "Net-(U3B-PF5)") (class "Default")
      (node (ref "R213") (pin "1") (pinfunction "1_1") (pintype "passive"))
      (node (ref "U3") (pin "K3") (pinfunction "PF5_K3") (pintype "passive"))
    )
    (net (code "284") (name "Net-(U3B-PF11)") (class "Default")
      (node (ref "R52") (pin "1") (pinfunction "1_1") (pintype "passive"))
      (node (ref "U3") (pin "P8") (pinfunction "PF11_P8") (pintype "passive"))
    )
    (net (code "285") (name "Net-(U3B-PF12)") (class "Default")
      (node (ref "R253") (pin "1") (pinfunction "1_1") (pintype "passive"))
      (node (ref "U3") (pin "M6") (pinfunction "PF12_M6") (pintype "passive"))
    )
    (net (code "286") (name "Net-(U3B-PF13)") (class "Default")
      (node (ref "R250") (pin "1") (pinfunction "1_1") (pintype "passive"))
      (node (ref "U3") (pin "N6") (pinfunction "PF13_N6") (pintype "passive"))
    )
    (net (code "287") (name "Net-(U3B-PF14)") (class "Default")
      (node (ref "R254") (pin "1") (pinfunction "1_1") (pintype "passive"))
      (node (ref "U3") (pin "P6") (pinfunction "PF14_P6") (pintype "passive"))
    )
    (net (code "288") (name "Net-(U3B-PF15)") (class "Default")
      (node (ref "R273") (pin "1") (pinfunction "1_1") (pintype "passive"))
      (node (ref "U3") (pin "M8") (pinfunction "PF15_M8") (pintype "passive"))
    )
    (net (code "289") (name "Net-(U3B-PG0)") (class "Default")
      (node (ref "R258") (pin "1") (pinfunction "1_1") (pintype "passive"))
      (node (ref "U3") (pin "N7") (pinfunction "PG0_N7") (pintype "passive"))
    )
    (net (code "290") (name "Net-(U3B-PG1)") (class "Default")
      (node (ref "R257") (pin "1") (pinfunction "1_1") (pintype "passive"))
      (node (ref "U3") (pin "M7") (pinfunction "PG1_M7") (pintype "passive"))
    )
    (net (code "291") (name "Net-(U3B-PG2)") (class "Default")
      (node (ref "R285") (pin "1") (pinfunction "1_1") (pintype "passive"))
      (node (ref "U3") (pin "M13") (pinfunction "PG2_M13") (pintype "passive"))
    )
    (net (code "292") (name "Net-(U3B-PG3)") (class "Default")
      (node (ref "R269") (pin "1") (pinfunction "1_1") (pintype "passive"))
      (node (ref "U3") (pin "M12") (pinfunction "PG3_M12") (pintype "passive"))
    )
    (net (code "293") (name "Net-(U3B-PG4)") (class "Default")
      (node (ref "R286") (pin "1") (pinfunction "1_1") (pintype "passive"))
      (node (ref "U3") (pin "N12") (pinfunction "PG4_N12") (pintype "passive"))
    )
    (net (code "294") (name "Net-(U3B-PG5)") (class "Default")
      (node (ref "R271") (pin "1") (pinfunction "1_1") (pintype "passive"))
      (node (ref "U3") (pin "N11") (pinfunction "PG5_N11") (pintype "passive"))
    )
    (net (code "295") (name "Net-(U3B-PG8)") (class "Default")
      (node (ref "R62") (pin "1") (pinfunction "1_1") (pintype "passive"))
      (node (ref "U3") (pin "H14") (pinfunction "PG8_H14") (pintype "passive"))
    )
    (net (code "296") (name "Net-(U3B-PG15)") (class "Default")
      (node (ref "R42") (pin "1") (pinfunction "1_1") (pintype "passive"))
      (node (ref "U3") (pin "B7") (pinfunction "PG15_B7") (pintype "passive"))
    )
    (net (code "297") (name "Net-(U3B-PH3)") (class "Default")
      (node (ref "R248") (pin "2") (pinfunction "2_2") (pintype "passive"))
      (node (ref "SB8") (pin "1") (pinfunction "1_1") (pintype "passive"))
      (node (ref "U3") (pin "J4") (pinfunction "PH3_J4") (pintype "passive"))
    )
    (net (code "298") (name "Net-(U3B-PH5)") (class "Default")
      (node (ref "R251") (pin "2") (pinfunction "2_2") (pintype "passive"))
      (node (ref "U3") (pin "J3") (pinfunction "PH5_J3") (pintype "passive"))
    )
    (net (code "299") (name "Net-(U3B-PH8)") (class "Default")
      (node (ref "R57") (pin "2") (pinfunction "2_2") (pintype "passive"))
      (node (ref "U3") (pin "P14") (pinfunction "PH8_P14") (pintype "passive"))
    )
    (net (code "300") (name "Net-(U3B-PH9)") (class "Default")
      (node (ref "R58") (pin "2") (pinfunction "2_2") (pintype "passive"))
      (node (ref "U3") (pin "N14") (pinfunction "PH9_N14") (pintype "passive"))
    )
    (net (code "301") (name "Net-(U3B-PH10)") (class "Default")
      (node (ref "R70") (pin "2") (pinfunction "2_2") (pintype "passive"))
      (node (ref "U3") (pin "P15") (pinfunction "PH10_P15") (pintype "passive"))
    )
    (net (code "302") (name "Net-(U3B-PH11)") (class "Default")
      (node (ref "R71") (pin "2") (pinfunction "2_2") (pintype "passive"))
      (node (ref "U3") (pin "N15") (pinfunction "PH11_N15") (pintype "passive"))
    )
    (net (code "303") (name "Net-(U3B-PH12)") (class "Default")
      (node (ref "R59") (pin "2") (pinfunction "2_2") (pintype "passive"))
      (node (ref "U3") (pin "M15") (pinfunction "PH12_M15") (pintype "passive"))
    )
    (net (code "304") (name "Net-(U3B-PH13)") (class "Default")
      (node (ref "R278") (pin "2") (pinfunction "2_2") (pintype "passive"))
      (node (ref "U3") (pin "E12") (pinfunction "PH13_E12") (pintype "passive"))
    )
    (net (code "305") (name "Net-(U3B-PH14)") (class "Default")
      (node (ref "R291") (pin "2") (pinfunction "2_2") (pintype "passive"))
      (node (ref "U3") (pin "E13") (pinfunction "PH14_E13") (pintype "passive"))
    )
    (net (code "306") (name "Net-(U3B-PH15)") (class "Default")
      (node (ref "R290") (pin "2") (pinfunction "2_2") (pintype "passive"))
      (node (ref "U3") (pin "D13") (pinfunction "PH15_D13") (pintype "passive"))
    )
    (net (code "307") (name "Net-(U3B-PI0)") (class "Default")
      (node (ref "R277") (pin "2") (pinfunction "2_2") (pintype "passive"))
      (node (ref "U3") (pin "E14") (pinfunction "PI0_E14") (pintype "passive"))
    )
    (net (code "308") (name "Net-(U3B-PI1)") (class "Default")
      (node (ref "R276") (pin "2") (pinfunction "2_2") (pintype "passive"))
      (node (ref "U3") (pin "D14") (pinfunction "PI1_D14") (pintype "passive"))
    )
    (net (code "309") (name "Net-(U3B-PI2)") (class "Default")
      (node (ref "R275") (pin "2") (pinfunction "2_2") (pintype "passive"))
      (node (ref "U3") (pin "C14") (pinfunction "PI2_C14") (pintype "passive"))
    )
    (net (code "310") (name "Net-(U3B-PI3)") (class "Default")
      (node (ref "R289") (pin "2") (pinfunction "2_2") (pintype "passive"))
      (node (ref "U3") (pin "C13") (pinfunction "PI3_C13") (pintype "passive"))
    )
    (net (code "311") (name "Net-(U3B-PI6)") (class "Default")
      (node (ref "R247") (pin "2") (pinfunction "2_2") (pintype "passive"))
      (node (ref "U3") (pin "D6") (pinfunction "PI6_D6") (pintype "passive"))
    )
    (net (code "312") (name "Net-(U3B-PI7)") (class "Default")
      (node (ref "R237") (pin "2") (pinfunction "2_2") (pintype "passive"))
      (node (ref "U3") (pin "D4") (pinfunction "PI7_D4") (pintype "passive"))
    )
    (net (code "313") (name "Net-(U3B-PI9)") (class "Default")
      (node (ref "R241") (pin "2") (pinfunction "2_2") (pintype "passive"))
      (node (ref "U3") (pin "E4") (pinfunction "PI9_E4") (pintype "passive"))
    )
    (net (code "314") (name "Net-(U3B-PI10)") (class "Default")
      (node (ref "R244") (pin "2") (pinfunction "2_2") (pintype "passive"))
      (node (ref "R43") (pin "2") (pinfunction "2_2") (pintype "passive"))
      (node (ref "U3") (pin "D5") (pinfunction "PI10_D5") (pintype "passive"))
    )
    (net (code "315") (name "Net-(U3B-PI14)") (class "Default")
      (node (ref "R295") (pin "2") (pinfunction "2_2") (pintype "passive"))
      (node (ref "U3") (pin "H3") (pinfunction "PI14_H3") (pintype "passive"))
    )
    (net (code "316") (name "Net-(U3C-BYPASS-REG)") (class "Default")
      (node (ref "R245") (pin "2") (pinfunction "2_2") (pintype "passive"))
      (node (ref "U3") (pin "L5") (pinfunction "BYPASS-REG_L5") (pintype "passive"))
    )
    (net (code "317") (name "Net-(U3C-VBAT)") (class "Default")
      (node (ref "JP8") (pin "2") (pintype "passive"))
      (node (ref "U3") (pin "C1") (pinfunction "VBAT_C1") (pintype "passive"))
    )
    (net (code "318") (name "Net-(U3C-VCAP1)") (class "Default")
      (node (ref "C133") (pin "1") (pinfunction "1_1") (pintype "passive"))
      (node (ref "U3") (pin "L11") (pinfunction "VCAP1_L11") (pintype "passive"))
    )
    (net (code "319") (name "Net-(U3C-VCAP2)") (class "Default")
      (node (ref "C32") (pin "1") (pinfunction "1_1") (pintype "passive"))
      (node (ref "U3") (pin "E11") (pinfunction "VCAP2_E11") (pintype "passive"))
    )
    (net (code "320") (name "VBUS_FS1") (class "Default")
      (node (ref "R266") (pin "2") (pinfunction "2_2") (pintype "passive"))
    )
    (net (code "321") (name "VBUS_FS2") (class "Default")
      (node (ref "R264") (pin "1") (pinfunction "1_1") (pintype "passive"))
    )
    (net (code "322") (name "VDDA") (class "Default")
      (node (ref "C108") (pin "1") (pinfunction "1_1") (pintype "passive"))
      (node (ref "C110") (pin "2") (pinfunction "2_2") (pintype "passive"))
      (node (ref "L10") (pin "2") (pinfunction "2_2") (pintype "passive"))
      (node (ref "R31") (pin "1") (pinfunction "1_1") (pintype "passive"))
      (node (ref "TP5") (pin "1") (pinfunction "1_1") (pintype "passive"))
      (node (ref "U3") (pin "R1") (pinfunction "VDDA_R1") (pintype "passive"))
    )
    (net (code "323") (name "VDD_MCU") (class "Default")
      (node (ref "C104") (pin "1") (pinfunction "1_1") (pintype "passive"))
      (node (ref "C105") (pin "1") (pinfunction "1_1") (pintype "passive"))
      (node (ref "C106") (pin "1") (pinfunction "1_1") (pintype "passive"))
      (node (ref "C109") (pin "1") (pinfunction "1_1") (pintype "passive"))
      (node (ref "C111") (pin "1") (pinfunction "1_1") (pintype "passive"))
      (node (ref "C112") (pin "1") (pinfunction "1_1") (pintype "passive"))
      (node (ref "C113") (pin "1") (pinfunction "1_1") (pintype "passive"))
      (node (ref "C114") (pin "1") (pinfunction "1_1") (pintype "passive"))
      (node (ref "C115") (pin "1") (pinfunction "1_1") (pintype "passive"))
      (node (ref "C118") (pin "1") (pinfunction "1_1") (pintype "passive"))
      (node (ref "C119") (pin "1") (pinfunction "1_1") (pintype "passive"))
      (node (ref "C120") (pin "1") (pinfunction "1_1") (pintype "passive"))
      (node (ref "C121") (pin "1") (pinfunction "1_1") (pintype "passive"))
      (node (ref "C122") (pin "1") (pinfunction "1_1") (pintype "passive"))
      (node (ref "C123") (pin "1") (pinfunction "1_1") (pintype "passive"))
      (node (ref "C125") (pin "1") (pinfunction "1_1") (pintype "passive"))
      (node (ref "C126") (pin "1") (pinfunction "1_1") (pintype "passive"))
      (node (ref "C127") (pin "1") (pinfunction "1_1") (pintype "passive"))
      (node (ref "C128") (pin "1") (pinfunction "1_1") (pintype "passive"))
      (node (ref "C129") (pin "1") (pinfunction "1_1") (pintype "passive"))
      (node (ref "C130") (pin "1") (pinfunction "1_1") (pintype "passive"))
      (node (ref "L10") (pin "1") (pinfunction "1_1") (pintype "passive"))
      (node (ref "U3") (pin "E10") (pinfunction "VDD15_E10") (pintype "passive"))
      (node (ref "U3") (pin "E7") (pinfunction "VDD3_E7") (pintype "passive"))
      (node (ref "U3") (pin "E8") (pinfunction "VDD11_E8") (pintype "passive"))
      (node (ref "U3") (pin "E9") (pinfunction "VDD10_E9") (pintype "passive"))
      (node (ref "U3") (pin "F11") (pinfunction "VDD2_F11") (pintype "passive"))
      (node (ref "U3") (pin "F4") (pinfunction "VDD13_F4") (pintype "passive"))
      (node (ref "U3") (pin "F5") (pinfunction "VDD17_F5") (pintype "passive"))
      (node (ref "U3") (pin "G11") (pinfunction "VDD9_G11") (pintype "passive"))
      (node (ref "U3") (pin "G5") (pinfunction "VDD18_G5") (pintype "passive"))
      (node (ref "U3") (pin "H11") (pinfunction "VDD20_H11") (pintype "passive"))
      (node (ref "U3") (pin "H5") (pinfunction "VDD5_H5") (pintype "passive"))
      (node (ref "U3") (pin "J11") (pinfunction "VDD8_J11") (pintype "passive"))
      (node (ref "U3") (pin "J5") (pinfunction "VDD12_J5") (pintype "passive"))
      (node (ref "U3") (pin "K11") (pinfunction "VDD14_K11") (pintype "passive"))
      (node (ref "U3") (pin "K5") (pinfunction "VDD4_K5") (pintype "passive"))
      (node (ref "U3") (pin "L10") (pinfunction "VDD1_L10") (pintype "passive"))
      (node (ref "U3") (pin "L7") (pinfunction "VDD19_L7") (pintype "passive"))
      (node (ref "U3") (pin "L8") (pinfunction "VDD6_L8") (pintype "passive"))
      (node (ref "U3") (pin "L9") (pinfunction "VDD7_L9") (pintype "passive"))
    )
    (net (code "324") (name "VREF+") (class "Default")
      (node (ref "C103") (pin "1") (pinfunction "1_1") (pintype "passive"))
      (node (ref "C107") (pin "2") (pinfunction "2_2") (pintype "passive"))
      (node (ref "R31") (pin "2") (pinfunction "2_2") (pintype "passive"))
      (node (ref "TP2") (pin "1") (pinfunction "1_1") (pintype "passive"))
      (node (ref "U3") (pin "P1") (pinfunction "VREF+_P1") (pintype "passive"))
    )
    (net (code "325") (name "unconnected-(X1-Pad2)") (class "Default")
      (node (ref "X1") (pin "2") (pinfunction "2_2") (pintype "passive"))
    )
    (net (code "326") (name "unconnected-(X1-Pad3)") (class "Default")
      (node (ref "X1") (pin "3") (pinfunction "3_3") (pintype "passive"))
    )
  )
)
